# 11_MCU.net
KiCad netlist of a schematic drawn in Altium Designer
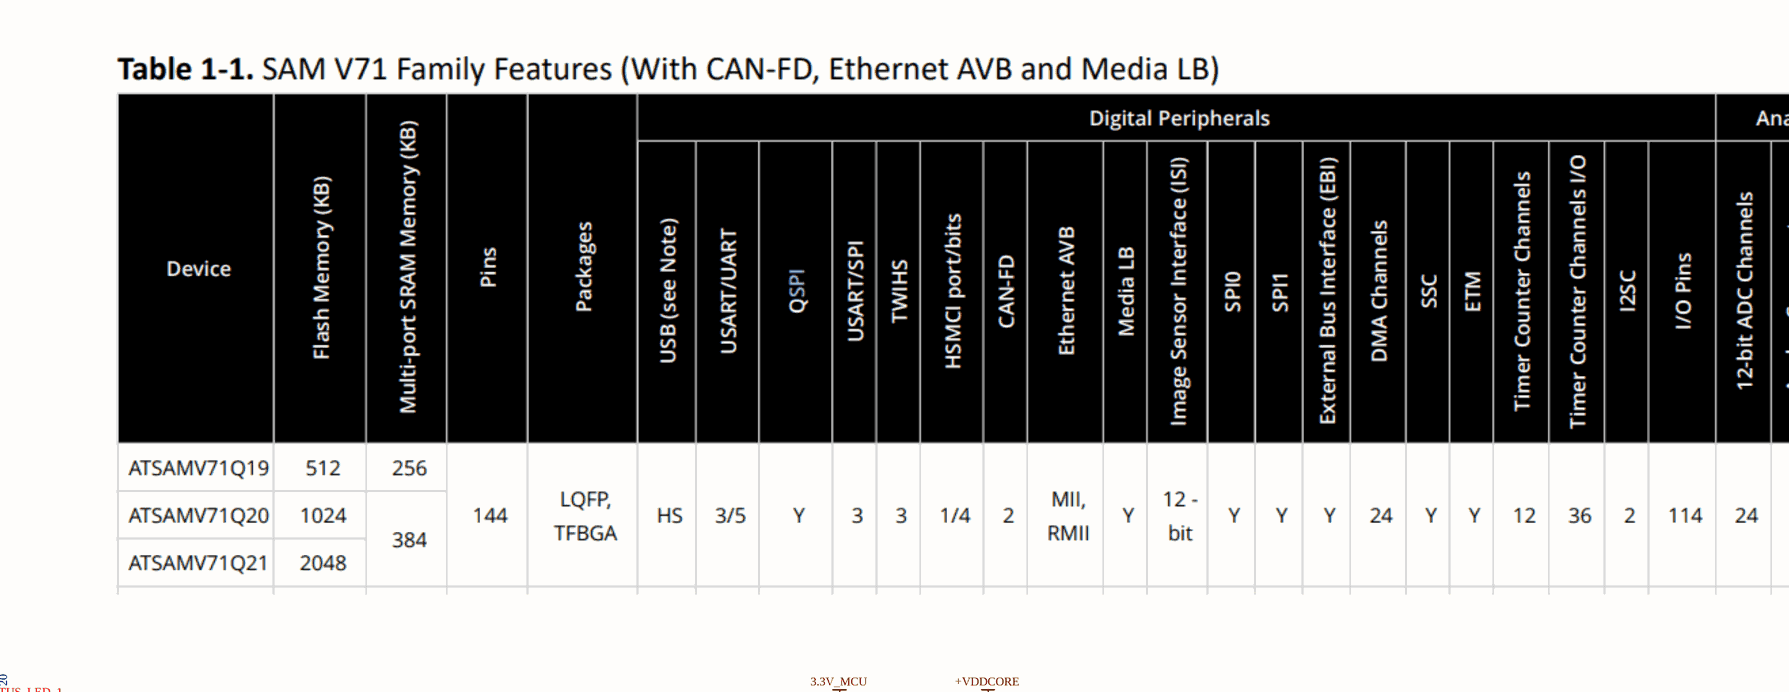
[diagram p0: 11_MCU.SchDoc, top left]
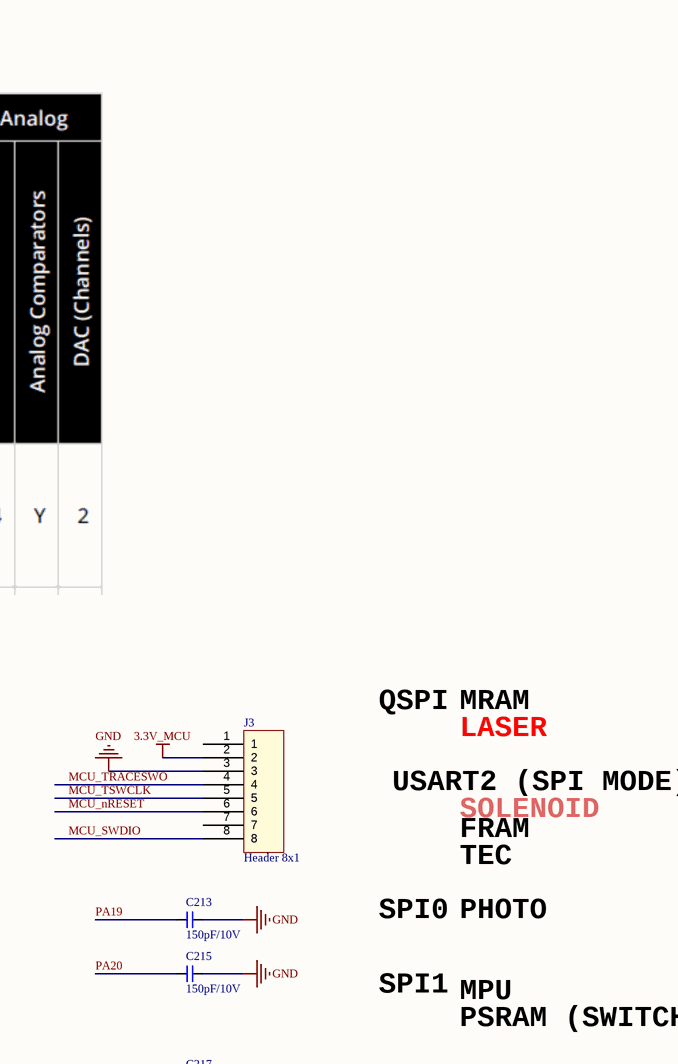
[diagram p1: 11_MCU.SchDoc, top right]
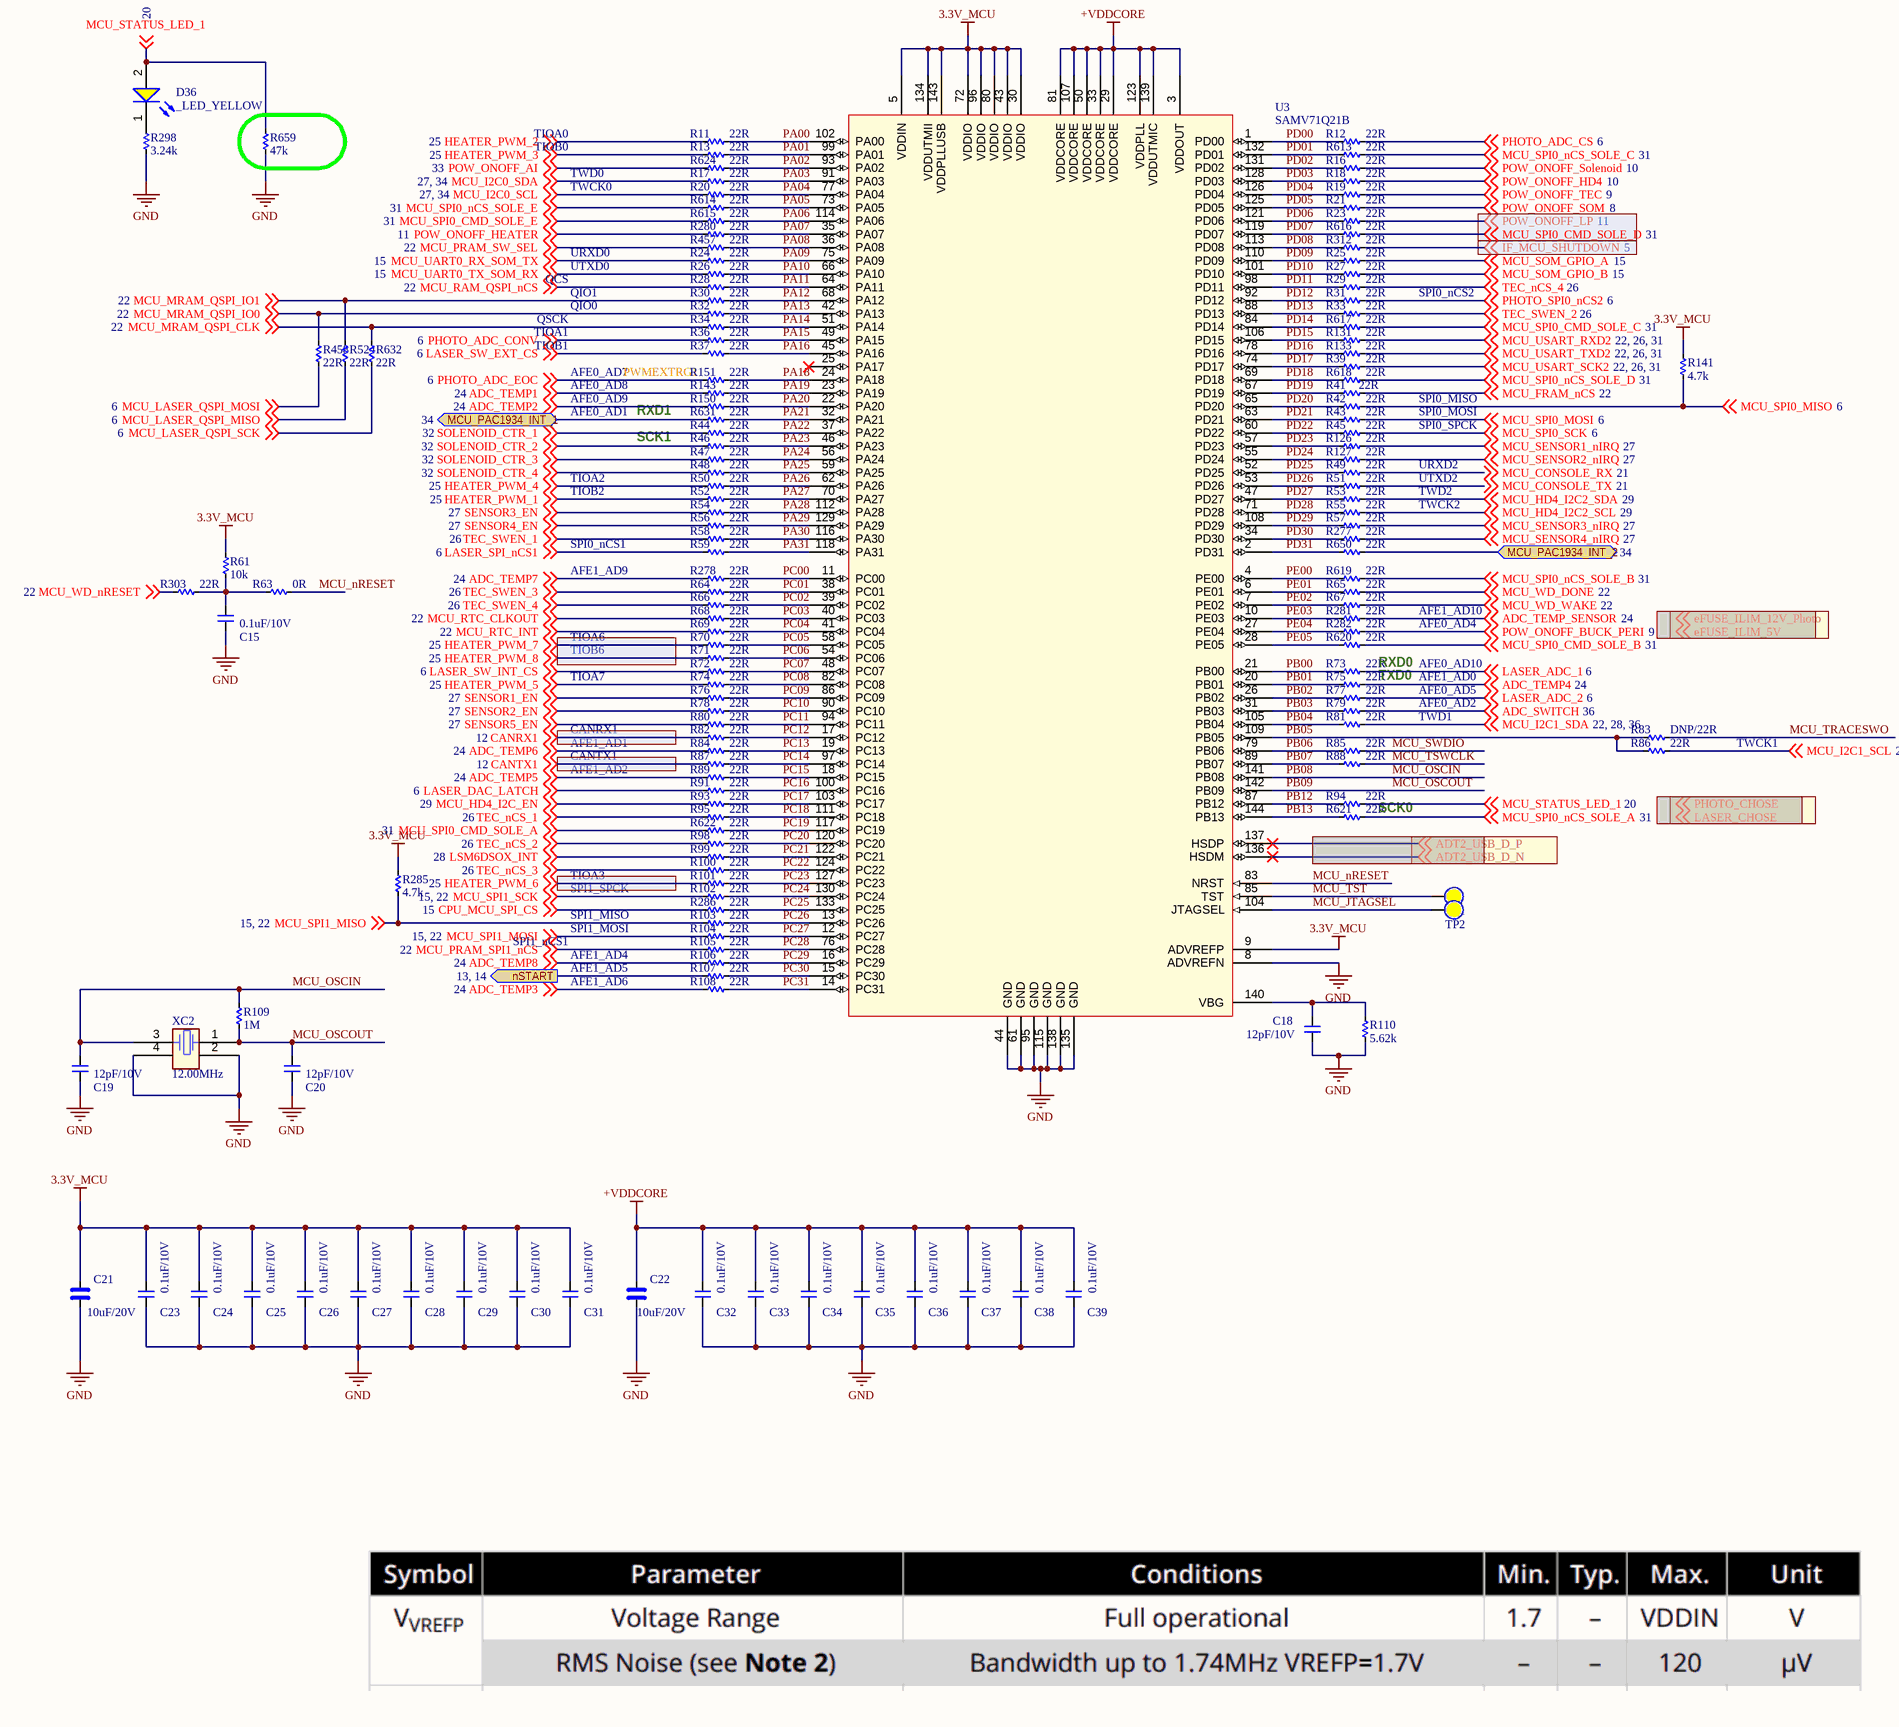
[diagram p2: 11_MCU.SchDoc, bottom left]
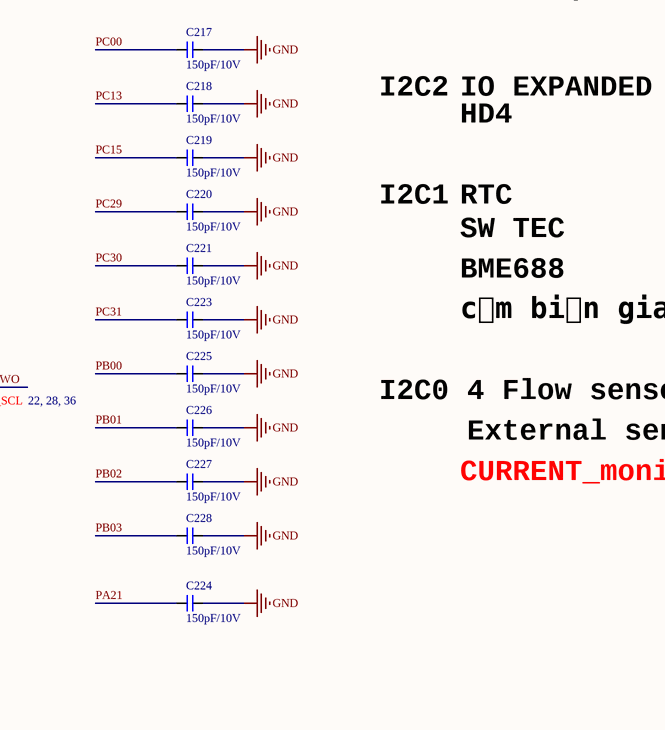
[diagram p3: 11_MCU.SchDoc, bottom right]

(export (version "E")
  (design (tool "Eeschema 10.0.6"))
  (components
    (comp (ref "C15")
      (value "0.1uF/10V")
      (footprint "CAP_C_1005X60")
      (description "CAP")
      (libsource (lib "LABLIB") (part "_CAP_C_2"))
    )
    (comp (ref "C18")
      (value "12pF/10V")
      (footprint "CAP_C_1005X60")
      (description "CAP")
      (libsource (lib "LABLIB") (part "_CAP_C_2"))
    )
    (comp (ref "C19")
      (value "12pF/10V")
      (footprint "CAP_C_1005X60")
      (description "CAP")
      (libsource (lib "LABLIB") (part "_CAP_C_2"))
    )
    (comp (ref "C20")
      (value "12pF/10V")
      (footprint "CAP_C_1005X60")
      (description "CAP")
      (libsource (lib "LABLIB") (part "_CAP_C_2"))
    )
    (comp (ref "C21")
      (value "10uF/20V")
      (footprint "CAP_C_2012X110")
      (description "CAP High Value")
      (libsource (lib "LABLIB") (part "_CAP_C_High_2"))
    )
    (comp (ref "C22")
      (value "10uF/20V")
      (footprint "CAP_C_2012X110")
      (description "CAP High Value")
      (libsource (lib "LABLIB") (part "_CAP_C_High_2"))
    )
    (comp (ref "C23")
      (value "0.1uF/10V")
      (footprint "CAP_C_1005X60")
      (description "CAP")
      (libsource (lib "LABLIB") (part "_CAP_C_2"))
    )
    (comp (ref "C24")
      (value "0.1uF/10V")
      (footprint "CAP_C_1005X60")
      (description "CAP")
      (libsource (lib "LABLIB") (part "_CAP_C_2"))
    )
    (comp (ref "C25")
      (value "0.1uF/10V")
      (footprint "CAP_C_1005X60")
      (description "CAP")
      (libsource (lib "LABLIB") (part "_CAP_C_2"))
    )
    (comp (ref "C26")
      (value "0.1uF/10V")
      (footprint "CAP_C_1005X60")
      (description "CAP")
      (libsource (lib "LABLIB") (part "_CAP_C_2"))
    )
    (comp (ref "C27")
      (value "0.1uF/10V")
      (footprint "CAP_C_1005X60")
      (description "CAP")
      (libsource (lib "LABLIB") (part "_CAP_C_2"))
    )
    (comp (ref "C28")
      (value "0.1uF/10V")
      (footprint "CAP_C_1005X60")
      (description "CAP")
      (libsource (lib "LABLIB") (part "_CAP_C_2"))
    )
    (comp (ref "C29")
      (value "0.1uF/10V")
      (footprint "CAP_C_1005X60")
      (description "CAP")
      (libsource (lib "LABLIB") (part "_CAP_C_2"))
    )
    (comp (ref "C30")
      (value "0.1uF/10V")
      (footprint "CAP_C_1005X60")
      (description "CAP")
      (libsource (lib "LABLIB") (part "_CAP_C_2"))
    )
    (comp (ref "C31")
      (value "0.1uF/10V")
      (footprint "CAP_C_1005X60")
      (description "CAP")
      (libsource (lib "LABLIB") (part "_CAP_C_2"))
    )
    (comp (ref "C32")
      (value "0.1uF/10V")
      (footprint "CAP_C_1005X60")
      (description "CAP")
      (libsource (lib "LABLIB") (part "_CAP_C_2"))
    )
    (comp (ref "C33")
      (value "0.1uF/10V")
      (footprint "CAP_C_1005X60")
      (description "CAP")
      (libsource (lib "LABLIB") (part "_CAP_C_2"))
    )
    (comp (ref "C34")
      (value "0.1uF/10V")
      (footprint "CAP_C_1005X60")
      (description "CAP")
      (libsource (lib "LABLIB") (part "_CAP_C_2"))
    )
    (comp (ref "C35")
      (value "0.1uF/10V")
      (footprint "CAP_C_1005X60")
      (description "CAP")
      (libsource (lib "LABLIB") (part "_CAP_C_2"))
    )
    (comp (ref "C36")
      (value "0.1uF/10V")
      (footprint "CAP_C_1005X60")
      (description "CAP")
      (libsource (lib "LABLIB") (part "_CAP_C_2"))
    )
    (comp (ref "C37")
      (value "0.1uF/10V")
      (footprint "CAP_C_1005X60")
      (description "CAP")
      (libsource (lib "LABLIB") (part "_CAP_C_2"))
    )
    (comp (ref "C38")
      (value "0.1uF/10V")
      (footprint "CAP_C_1005X60")
      (description "CAP")
      (libsource (lib "LABLIB") (part "_CAP_C_2"))
    )
    (comp (ref "C39")
      (value "0.1uF/10V")
      (footprint "CAP_C_1005X60")
      (description "CAP")
      (libsource (lib "LABLIB") (part "_CAP_C_2"))
    )
    (comp (ref "C213")
      (value "150pF/10V")
      (footprint "CAP_C_1005X60")
      (description "CAP")
      (libsource (lib "LABLIB") (part "_CAP_C_2"))
    )
    (comp (ref "C215")
      (value "150pF/10V")
      (footprint "CAP_C_1005X60")
      (description "CAP")
      (libsource (lib "LABLIB") (part "_CAP_C_2"))
    )
    (comp (ref "C217")
      (value "150pF/10V")
      (footprint "CAP_C_1005X60")
      (description "CAP")
      (libsource (lib "LABLIB") (part "_CAP_C_2"))
    )
    (comp (ref "C218")
      (value "150pF/10V")
      (footprint "CAP_C_1005X60")
      (description "CAP")
      (libsource (lib "LABLIB") (part "_CAP_C_2"))
    )
    (comp (ref "C219")
      (value "150pF/10V")
      (footprint "CAP_C_1005X60")
      (description "CAP")
      (libsource (lib "LABLIB") (part "_CAP_C_2"))
    )
    (comp (ref "C220")
      (value "150pF/10V")
      (footprint "CAP_C_1005X60")
      (description "CAP")
      (libsource (lib "LABLIB") (part "_CAP_C_2"))
    )
    (comp (ref "C221")
      (value "150pF/10V")
      (footprint "CAP_C_1005X60")
      (description "CAP")
      (libsource (lib "LABLIB") (part "_CAP_C_2"))
    )
    (comp (ref "C223")
      (value "150pF/10V")
      (footprint "CAP_C_1005X60")
      (description "CAP")
      (libsource (lib "LABLIB") (part "_CAP_C_2"))
    )
    (comp (ref "C224")
      (value "150pF/10V")
      (footprint "CAP_C_1005X60")
      (description "CAP")
      (libsource (lib "LABLIB") (part "_CAP_C_2"))
    )
    (comp (ref "C225")
      (value "150pF/10V")
      (footprint "CAP_C_1005X60")
      (description "CAP")
      (libsource (lib "LABLIB") (part "_CAP_C_2"))
    )
    (comp (ref "C226")
      (value "150pF/10V")
      (footprint "CAP_C_1005X60")
      (description "CAP")
      (libsource (lib "LABLIB") (part "_CAP_C_2"))
    )
    (comp (ref "C227")
      (value "150pF/10V")
      (footprint "CAP_C_1005X60")
      (description "CAP")
      (libsource (lib "LABLIB") (part "_CAP_C_2"))
    )
    (comp (ref "C228")
      (value "150pF/10V")
      (footprint "CAP_C_1005X60")
      (description "CAP")
      (libsource (lib "LABLIB") (part "_CAP_C_2"))
    )
    (comp (ref "D36")
      (value "_LED_YELLOW")
      (footprint "LED_0603")
      (libsource (lib "LABLIB") (part "_LED_YELLOW"))
    )
    (comp (ref "J3")
      (value "Header 8x1")
      (footprint "Header_254P_8x1")
      (libsource (lib "LABLIB") (part "Header 8x1"))
    )
    (comp (ref "R11")
      (value "22R")
      (footprint "RES_C_1005X40")
      (description "RES")
      (libsource (lib "LABLIB") (part "_RES_B_2"))
    )
    (comp (ref "R12")
      (value "22R")
      (footprint "RES_C_1005X40")
      (description "RES")
      (libsource (lib "LABLIB") (part "_RES_B_2"))
    )
    (comp (ref "R13")
      (value "22R")
      (footprint "RES_C_1005X40")
      (description "RES")
      (libsource (lib "LABLIB") (part "_RES_B_2"))
    )
    (comp (ref "R16")
      (value "22R")
      (footprint "RES_C_1005X40")
      (description "RES")
      (libsource (lib "LABLIB") (part "_RES_B_2"))
    )
    (comp (ref "R17")
      (value "22R")
      (footprint "RES_C_1005X40")
      (description "RES")
      (libsource (lib "LABLIB") (part "_RES_B_2"))
    )
    (comp (ref "R18")
      (value "22R")
      (footprint "RES_C_1005X40")
      (description "RES")
      (libsource (lib "LABLIB") (part "_RES_B_2"))
    )
    (comp (ref "R19")
      (value "22R")
      (footprint "RES_C_1005X40")
      (description "RES")
      (libsource (lib "LABLIB") (part "_RES_B_2"))
    )
    (comp (ref "R20")
      (value "22R")
      (footprint "RES_C_1005X40")
      (description "RES")
      (libsource (lib "LABLIB") (part "_RES_B_2"))
    )
    (comp (ref "R21")
      (value "22R")
      (footprint "RES_C_1005X40")
      (description "RES")
      (libsource (lib "LABLIB") (part "_RES_B_2"))
    )
    (comp (ref "R23")
      (value "22R")
      (footprint "RES_C_1005X40")
      (description "RES")
      (libsource (lib "LABLIB") (part "_RES_B_2"))
    )
    (comp (ref "R24")
      (value "22R")
      (footprint "RES_C_1005X40")
      (description "RES")
      (libsource (lib "LABLIB") (part "_RES_B_2"))
    )
    (comp (ref "R25")
      (value "22R")
      (footprint "RES_C_1005X40")
      (description "RES")
      (libsource (lib "LABLIB") (part "_RES_B_2"))
    )
    (comp (ref "R26")
      (value "22R")
      (footprint "RES_C_1005X40")
      (description "RES")
      (libsource (lib "LABLIB") (part "_RES_B_2"))
    )
    (comp (ref "R27")
      (value "22R")
      (footprint "RES_C_1005X40")
      (description "RES")
      (libsource (lib "LABLIB") (part "_RES_B_2"))
    )
    (comp (ref "R28")
      (value "22R")
      (footprint "RES_C_1005X40")
      (description "RES")
      (libsource (lib "LABLIB") (part "_RES_B_2"))
    )
    (comp (ref "R29")
      (value "22R")
      (footprint "RES_C_1005X40")
      (description "RES")
      (libsource (lib "LABLIB") (part "_RES_B_2"))
    )
    (comp (ref "R30")
      (value "22R")
      (footprint "RES_C_1005X40")
      (description "RES")
      (libsource (lib "LABLIB") (part "_RES_B_2"))
    )
    (comp (ref "R31")
      (value "22R")
      (footprint "RES_C_1005X40")
      (description "RES")
      (libsource (lib "LABLIB") (part "_RES_B_2"))
    )
    (comp (ref "R32")
      (value "22R")
      (footprint "RES_C_1005X40")
      (description "RES")
      (libsource (lib "LABLIB") (part "_RES_B_2"))
    )
    (comp (ref "R33")
      (value "22R")
      (footprint "RES_C_1005X40")
      (description "RES")
      (libsource (lib "LABLIB") (part "_RES_B_2"))
    )
    (comp (ref "R34")
      (value "22R")
      (footprint "RES_C_1005X40")
      (description "RES")
      (libsource (lib "LABLIB") (part "_RES_B_2"))
    )
    (comp (ref "R36")
      (value "22R")
      (footprint "RES_C_1005X40")
      (description "RES")
      (libsource (lib "LABLIB") (part "_RES_B_2"))
    )
    (comp (ref "R37")
      (value "22R")
      (footprint "RES_C_1005X40")
      (description "RES")
      (libsource (lib "LABLIB") (part "_RES_B_2"))
    )
    (comp (ref "R39")
      (value "22R")
      (footprint "RES_C_1005X40")
      (description "RES")
      (libsource (lib "LABLIB") (part "_RES_B_2"))
    )
    (comp (ref "R41")
      (value "22R")
      (footprint "RES_C_1005X40")
      (description "RES")
      (libsource (lib "LABLIB") (part "_RES_B_2"))
    )
    (comp (ref "R42")
      (value "22R")
      (footprint "RES_C_1005X40")
      (description "RES")
      (libsource (lib "LABLIB") (part "_RES_B_2"))
    )
    (comp (ref "R43")
      (value "22R")
      (footprint "RES_C_1005X40")
      (description "RES")
      (libsource (lib "LABLIB") (part "_RES_B_2"))
    )
    (comp (ref "R44")
      (value "22R")
      (footprint "RES_C_1005X40")
      (description "RES")
      (libsource (lib "LABLIB") (part "_RES_B_2"))
    )
    (comp (ref "R45")
      (value "22R")
      (footprint "RES_C_1005X40")
      (description "RES")
      (libsource (lib "LABLIB") (part "_RES_B_2"))
    )
    (comp (ref "R46")
      (value "22R")
      (footprint "RES_C_1005X40")
      (description "RES")
      (libsource (lib "LABLIB") (part "_RES_B_2"))
    )
    (comp (ref "R47")
      (value "22R")
      (footprint "RES_C_1005X40")
      (description "RES")
      (libsource (lib "LABLIB") (part "_RES_B_2"))
    )
    (comp (ref "R48")
      (value "22R")
      (footprint "RES_C_1005X40")
      (description "RES")
      (libsource (lib "LABLIB") (part "_RES_B_2"))
    )
    (comp (ref "R49")
      (value "22R")
      (footprint "RES_C_1005X40")
      (description "RES")
      (libsource (lib "LABLIB") (part "_RES_B_2"))
    )
    (comp (ref "R50")
      (value "22R")
      (footprint "RES_C_1005X40")
      (description "RES")
      (libsource (lib "LABLIB") (part "_RES_B_2"))
    )
    (comp (ref "R51")
      (value "22R")
      (footprint "RES_C_1005X40")
      (description "RES")
      (libsource (lib "LABLIB") (part "_RES_B_2"))
    )
    (comp (ref "R52")
      (value "22R")
      (footprint "RES_C_1005X40")
      (description "RES")
      (libsource (lib "LABLIB") (part "_RES_B_2"))
    )
    (comp (ref "R53")
      (value "22R")
      (footprint "RES_C_1005X40")
      (description "RES")
      (libsource (lib "LABLIB") (part "_RES_B_2"))
    )
    (comp (ref "R54")
      (value "22R")
      (footprint "RES_C_1005X40")
      (description "RES")
      (libsource (lib "LABLIB") (part "_RES_B_2"))
    )
    (comp (ref "R55")
      (value "22R")
      (footprint "RES_C_1005X40")
      (description "RES")
      (libsource (lib "LABLIB") (part "_RES_B_2"))
    )
    (comp (ref "R56")
      (value "22R")
      (footprint "RES_C_1005X40")
      (description "RES")
      (libsource (lib "LABLIB") (part "_RES_B_2"))
    )
    (comp (ref "R57")
      (value "22R")
      (footprint "RES_C_1005X40")
      (description "RES")
      (libsource (lib "LABLIB") (part "_RES_B_2"))
    )
    (comp (ref "R58")
      (value "22R")
      (footprint "RES_C_1005X40")
      (description "RES")
      (libsource (lib "LABLIB") (part "_RES_B_2"))
    )
    (comp (ref "R59")
      (value "22R")
      (footprint "RES_C_1005X40")
      (description "RES")
      (libsource (lib "LABLIB") (part "_RES_B_2"))
    )
    (comp (ref "R61")
      (value "10k")
      (footprint "RES_C_1005X40")
      (description "RES")
      (libsource (lib "LABLIB") (part "_RES_B_2"))
    )
    (comp (ref "R63")
      (value "0R")
      (footprint "RES_C_1005X40")
      (description "RES")
      (libsource (lib "LABLIB") (part "_RES_B_2"))
    )
    (comp (ref "R64")
      (value "22R")
      (footprint "RES_C_1005X40")
      (description "RES")
      (libsource (lib "LABLIB") (part "_RES_B_2"))
    )
    (comp (ref "R65")
      (value "22R")
      (footprint "RES_C_1005X40")
      (description "RES")
      (libsource (lib "LABLIB") (part "_RES_B_2"))
    )
    (comp (ref "R66")
      (value "22R")
      (footprint "RES_C_1005X40")
      (description "RES")
      (libsource (lib "LABLIB") (part "_RES_B_2"))
    )
    (comp (ref "R67")
      (value "22R")
      (footprint "RES_C_1005X40")
      (description "RES")
      (libsource (lib "LABLIB") (part "_RES_B_2"))
    )
    (comp (ref "R68")
      (value "22R")
      (footprint "RES_C_1005X40")
      (description "RES")
      (libsource (lib "LABLIB") (part "_RES_B_2"))
    )
    (comp (ref "R69")
      (value "22R")
      (footprint "RES_C_1005X40")
      (description "RES")
      (libsource (lib "LABLIB") (part "_RES_B_2"))
    )
    (comp (ref "R70")
      (value "22R")
      (footprint "RES_C_1005X40")
      (description "RES")
      (libsource (lib "LABLIB") (part "_RES_B_2"))
    )
    (comp (ref "R71")
      (value "22R")
      (footprint "RES_C_1005X40")
      (description "RES")
      (libsource (lib "LABLIB") (part "_RES_B_2"))
    )
    (comp (ref "R72")
      (value "22R")
      (footprint "RES_C_1005X40")
      (description "RES")
      (libsource (lib "LABLIB") (part "_RES_B_2"))
    )
    (comp (ref "R73")
      (value "22R")
      (footprint "RES_C_1005X40")
      (description "RES")
      (libsource (lib "LABLIB") (part "_RES_B_2"))
    )
    (comp (ref "R74")
      (value "22R")
      (footprint "RES_C_1005X40")
      (description "RES")
      (libsource (lib "LABLIB") (part "_RES_B_2"))
    )
    (comp (ref "R75")
      (value "22R")
      (footprint "RES_C_1005X40")
      (description "RES")
      (libsource (lib "LABLIB") (part "_RES_B_2"))
    )
    (comp (ref "R76")
      (value "22R")
      (footprint "RES_C_1005X40")
      (description "RES")
      (libsource (lib "LABLIB") (part "_RES_B_2"))
    )
    (comp (ref "R77")
      (value "22R")
      (footprint "RES_C_1005X40")
      (description "RES")
      (libsource (lib "LABLIB") (part "_RES_B_2"))
    )
    (comp (ref "R78")
      (value "22R")
      (footprint "RES_C_1005X40")
      (description "RES")
      (libsource (lib "LABLIB") (part "_RES_B_2"))
    )
    (comp (ref "R79")
      (value "22R")
      (footprint "RES_C_1005X40")
      (description "RES")
      (libsource (lib "LABLIB") (part "_RES_B_2"))
    )
    (comp (ref "R80")
      (value "22R")
      (footprint "RES_C_1005X40")
      (description "RES")
      (libsource (lib "LABLIB") (part "_RES_B_2"))
    )
    (comp (ref "R81")
      (value "22R")
      (footprint "RES_C_1005X40")
      (description "RES")
      (libsource (lib "LABLIB") (part "_RES_B_2"))
    )
    (comp (ref "R82")
      (value "22R")
      (footprint "RES_C_1005X40")
      (description "RES")
      (libsource (lib "LABLIB") (part "_RES_B_2"))
    )
    (comp (ref "R83")
      (value "DNP/22R")
      (footprint "RES_C_1005X40")
      (description "RES")
      (libsource (lib "LABLIB") (part "_RES_B_2"))
    )
    (comp (ref "R84")
      (value "22R")
      (footprint "RES_C_1005X40")
      (description "RES")
      (libsource (lib "LABLIB") (part "_RES_B_2"))
    )
    (comp (ref "R85")
      (value "22R")
      (footprint "RES_C_1005X40")
      (description "RES")
      (libsource (lib "LABLIB") (part "_RES_B_2"))
    )
    (comp (ref "R86")
      (value "22R")
      (footprint "RES_C_1005X40")
      (description "RES")
      (libsource (lib "LABLIB") (part "_RES_B_2"))
    )
    (comp (ref "R87")
      (value "22R")
      (footprint "RES_C_1005X40")
      (description "RES")
      (libsource (lib "LABLIB") (part "_RES_B_2"))
    )
    (comp (ref "R88")
      (value "22R")
      (footprint "RES_C_1005X40")
      (description "RES")
      (libsource (lib "LABLIB") (part "_RES_B_2"))
    )
    (comp (ref "R89")
      (value "22R")
      (footprint "RES_C_1005X40")
      (description "RES")
      (libsource (lib "LABLIB") (part "_RES_B_2"))
    )
    (comp (ref "R91")
      (value "22R")
      (footprint "RES_C_1005X40")
      (description "RES")
      (libsource (lib "LABLIB") (part "_RES_B_2"))
    )
    (comp (ref "R93")
      (value "22R")
      (footprint "RES_C_1005X40")
      (description "RES")
      (libsource (lib "LABLIB") (part "_RES_B_2"))
    )
    (comp (ref "R94")
      (value "22R")
      (footprint "RES_C_1005X40")
      (description "RES")
      (libsource (lib "LABLIB") (part "_RES_B_2"))
    )
    (comp (ref "R95")
      (value "22R")
      (footprint "RES_C_1005X40")
      (description "RES")
      (libsource (lib "LABLIB") (part "_RES_B_2"))
    )
    (comp (ref "R98")
      (value "22R")
      (footprint "RES_C_1005X40")
      (description "RES")
      (libsource (lib "LABLIB") (part "_RES_B_2"))
    )
    (comp (ref "R99")
      (value "22R")
      (footprint "RES_C_1005X40")
      (description "RES")
      (libsource (lib "LABLIB") (part "_RES_B_2"))
    )
    (comp (ref "R100")
      (value "22R")
      (footprint "RES_C_1005X40")
      (description "RES")
      (libsource (lib "LABLIB") (part "_RES_B_2"))
    )
    (comp (ref "R101")
      (value "22R")
      (footprint "RES_C_1005X40")
      (description "RES")
      (libsource (lib "LABLIB") (part "_RES_B_2"))
    )
    (comp (ref "R102")
      (value "22R")
      (footprint "RES_C_1005X40")
      (description "RES")
      (libsource (lib "LABLIB") (part "_RES_B_2"))
    )
    (comp (ref "R103")
      (value "22R")
      (footprint "RES_C_1005X40")
      (description "RES")
      (libsource (lib "LABLIB") (part "_RES_B_2"))
    )
    (comp (ref "R104")
      (value "22R")
      (footprint "RES_C_1005X40")
      (description "RES")
      (libsource (lib "LABLIB") (part "_RES_B_2"))
    )
    (comp (ref "R105")
      (value "22R")
      (footprint "RES_C_1005X40")
      (description "RES")
      (libsource (lib "LABLIB") (part "_RES_B_2"))
    )
    (comp (ref "R106")
      (value "22R")
      (footprint "RES_C_1005X40")
      (description "RES")
      (libsource (lib "LABLIB") (part "_RES_B_2"))
    )
    (comp (ref "R107")
      (value "22R")
      (footprint "RES_C_1005X40")
      (description "RES")
      (libsource (lib "LABLIB") (part "_RES_B_2"))
    )
    (comp (ref "R108")
      (value "22R")
      (footprint "RES_C_1005X40")
      (description "RES")
      (libsource (lib "LABLIB") (part "_RES_B_2"))
    )
    (comp (ref "R109")
      (value "1M")
      (footprint "RES_C_1005X40")
      (description "RES")
      (libsource (lib "LABLIB") (part "_RES_B_2"))
    )
    (comp (ref "R110")
      (value "5.62k")
      (footprint "RES_C_1005X40")
      (description "RES")
      (libsource (lib "LABLIB") (part "_RES_B_2"))
    )
    (comp (ref "R126")
      (value "22R")
      (footprint "RES_C_1005X40")
      (description "RES")
      (libsource (lib "LABLIB") (part "_RES_B_2"))
    )
    (comp (ref "R127")
      (value "22R")
      (footprint "RES_C_1005X40")
      (description "RES")
      (libsource (lib "LABLIB") (part "_RES_B_2"))
    )
    (comp (ref "R131")
      (value "22R")
      (footprint "RES_C_1005X40")
      (description "RES")
      (libsource (lib "LABLIB") (part "_RES_B_2"))
    )
    (comp (ref "R133")
      (value "22R")
      (footprint "RES_C_1005X40")
      (description "RES")
      (libsource (lib "LABLIB") (part "_RES_B_2"))
    )
    (comp (ref "R141")
      (value "4.7k")
      (footprint "RES_C_1005X40")
      (description "RES")
      (libsource (lib "LABLIB") (part "_RES_B_2"))
    )
    (comp (ref "R143")
      (value "22R")
      (footprint "RES_C_1005X40")
      (description "RES")
      (libsource (lib "LABLIB") (part "_RES_B_2"))
    )
    (comp (ref "R150")
      (value "22R")
      (footprint "RES_C_1005X40")
      (description "RES")
      (libsource (lib "LABLIB") (part "_RES_B_2"))
    )
    (comp (ref "R151")
      (value "22R")
      (footprint "RES_C_1005X40")
      (description "RES")
      (libsource (lib "LABLIB") (part "_RES_B_2"))
    )
    (comp (ref "R277")
      (value "22R")
      (footprint "RES_C_1005X40")
      (description "RES")
      (libsource (lib "LABLIB") (part "_RES_B_2"))
    )
    (comp (ref "R278")
      (value "22R")
      (footprint "RES_C_1005X40")
      (description "RES")
      (libsource (lib "LABLIB") (part "_RES_B_2"))
    )
    (comp (ref "R280")
      (value "22R")
      (footprint "RES_C_1005X40")
      (description "RES")
      (libsource (lib "LABLIB") (part "_RES_B_2"))
    )
    (comp (ref "R281")
      (value "22R")
      (footprint "RES_C_1005X40")
      (description "RES")
      (libsource (lib "LABLIB") (part "_RES_B_2"))
    )
    (comp (ref "R282")
      (value "22R")
      (footprint "RES_C_1005X40")
      (description "RES")
      (libsource (lib "LABLIB") (part "_RES_B_2"))
    )
    (comp (ref "R285")
      (value "4.7k")
      (footprint "RES_C_1005X40")
      (description "RES")
      (libsource (lib "LABLIB") (part "_RES_B_2"))
    )
    (comp (ref "R286")
      (value "22R")
      (footprint "RES_C_1005X40")
      (description "RES")
      (libsource (lib "LABLIB") (part "_RES_B_2"))
    )
    (comp (ref "R298")
      (value "3.24k")
      (footprint "RES_C_1005X40")
      (description "RES")
      (libsource (lib "LABLIB") (part "_RES_B_2"))
    )
    (comp (ref "R303")
      (value "22R")
      (footprint "RES_C_1005X40")
      (description "RES")
      (libsource (lib "LABLIB") (part "_RES_B_2"))
    )
    (comp (ref "R312")
      (value "22R")
      (footprint "RES_C_1005X40")
      (description "RES")
      (libsource (lib "LABLIB") (part "_RES_B_2"))
    )
    (comp (ref "R457")
      (value "22R")
      (footprint "RES_C_1005X40")
      (description "RES")
      (libsource (lib "LABLIB") (part "_RES_B_2"))
    )
    (comp (ref "R458")
      (value "22R")
      (footprint "RES_C_1005X40")
      (description "RES")
      (libsource (lib "LABLIB") (part "_RES_B_2"))
    )
    (comp (ref "R524")
      (value "22R")
      (footprint "RES_C_1005X40")
      (description "RES")
      (libsource (lib "LABLIB") (part "_RES_B_2"))
    )
    (comp (ref "R613")
      (value "22R")
      (footprint "RES_C_1005X40")
      (description "RES")
      (libsource (lib "LABLIB") (part "_RES_B_2"))
    )
    (comp (ref "R614")
      (value "22R")
      (footprint "RES_C_1005X40")
      (description "RES")
      (libsource (lib "LABLIB") (part "_RES_B_2"))
    )
    (comp (ref "R615")
      (value "22R")
      (footprint "RES_C_1005X40")
      (description "RES")
      (libsource (lib "LABLIB") (part "_RES_B_2"))
    )
    (comp (ref "R616")
      (value "22R")
      (footprint "RES_C_1005X40")
      (description "RES")
      (libsource (lib "LABLIB") (part "_RES_B_2"))
    )
    (comp (ref "R617")
      (value "22R")
      (footprint "RES_C_1005X40")
      (description "RES")
      (libsource (lib "LABLIB") (part "_RES_B_2"))
    )
    (comp (ref "R618")
      (value "22R")
      (footprint "RES_C_1005X40")
      (description "RES")
      (libsource (lib "LABLIB") (part "_RES_B_2"))
    )
    (comp (ref "R619")
      (value "22R")
      (footprint "RES_C_1005X40")
      (description "RES")
      (libsource (lib "LABLIB") (part "_RES_B_2"))
    )
    (comp (ref "R620")
      (value "22R")
      (footprint "RES_C_1005X40")
      (description "RES")
      (libsource (lib "LABLIB") (part "_RES_B_2"))
    )
    (comp (ref "R621")
      (value "22R")
      (footprint "RES_C_1005X40")
      (description "RES")
      (libsource (lib "LABLIB") (part "_RES_B_2"))
    )
    (comp (ref "R622")
      (value "22R")
      (footprint "RES_C_1005X40")
      (description "RES")
      (libsource (lib "LABLIB") (part "_RES_B_2"))
    )
    (comp (ref "R624")
      (value "22R")
      (footprint "RES_C_1005X40")
      (description "RES")
      (libsource (lib "LABLIB") (part "_RES_B_2"))
    )
    (comp (ref "R631")
      (value "22R")
      (footprint "RES_C_1005X40")
      (description "RES")
      (libsource (lib "LABLIB") (part "_RES_B_2"))
    )
    (comp (ref "R632")
      (value "22R")
      (footprint "RES_C_1005X40")
      (description "RES")
      (libsource (lib "LABLIB") (part "_RES_B_2"))
    )
    (comp (ref "R650")
      (value "22R")
      (footprint "RES_C_1005X40")
      (description "RES")
      (libsource (lib "LABLIB") (part "_RES_B_2"))
    )
    (comp (ref "R659")
      (value "47k")
      (footprint "RES_C_1608X60")
      (description "RES")
      (libsource (lib "LABLIB") (part "_RES_B_2"))
    )
    (comp (ref "TP1")
      (value "~")
      (footprint "Testpoint_80")
      (description "Test Point")
      (libsource (lib "LABLIB") (part "Test Point"))
    )
    (comp (ref "TP2")
      (value "~")
      (footprint "Testpoint_80")
      (description "Test Point")
      (libsource (lib "LABLIB") (part "Test Point"))
    )
    (comp (ref "U3")
      (value "SAMV71Q21B")
      (footprint "AP6-00118")
      (description "SAM 32-bit ARM Cortex-M* RISC MCU, SAMV71B Series, QFP144")
      (fields (field (name "MANUFACTURER") "MICROCHIP") (field (name "MPN") "ATSAMV71Q21B-AAB"))
      (libsource (lib "AltiumDbLib") (part "SAMV7_LQFP144"))
    )
    (comp (ref "XC2")
      (value "12.00MHz")
      (footprint "AP7-00039")
      (description "Fox FQ5032B 12.0MHz SMD crystal 738B-12")
      (fields (field (name "TOLERANCE") "Â±30ppm") (field (name "MANUFACTURER") "Fox  Electronics"))
      (libsource (lib "AltiumDbLib") (part "CRYSTAL1324"))
    )
  )
  (nets
    (net (code "1") (name "+VDDCORE") (class "Default")
      (node (ref "C22") (pin "1") (pinfunction "1_1") (pintype "passive"))
      (node (ref "C32") (pin "2") (pinfunction "2_2") (pintype "passive"))
      (node (ref "C33") (pin "2") (pinfunction "2_2") (pintype "passive"))
      (node (ref "C34") (pin "2") (pinfunction "2_2") (pintype "passive"))
      (node (ref "C35") (pin "2") (pinfunction "2_2") (pintype "passive"))
      (node (ref "C36") (pin "2") (pinfunction "2_2") (pintype "passive"))
      (node (ref "C37") (pin "2") (pinfunction "2_2") (pintype "passive"))
      (node (ref "C38") (pin "2") (pinfunction "2_2") (pintype "passive"))
      (node (ref "C39") (pin "2") (pinfunction "2_2") (pintype "passive"))
      (node (ref "U3") (pin "107") (pinfunction "VDDCORE_107") (pintype "power_in"))
      (node (ref "U3") (pin "123") (pinfunction "VDDPLL_123") (pintype "power_in"))
      (node (ref "U3") (pin "139") (pinfunction "VDDUTMIC_139") (pintype "power_in"))
      (node (ref "U3") (pin "29") (pinfunction "VDDCORE_29") (pintype "power_in"))
      (node (ref "U3") (pin "3") (pinfunction "VDDOUT_3") (pintype "power_in"))
      (node (ref "U3") (pin "33") (pinfunction "VDDCORE_33") (pintype "power_in"))
      (node (ref "U3") (pin "50") (pinfunction "VDDCORE_50") (pintype "power_in"))
      (node (ref "U3") (pin "81") (pinfunction "VDDCORE_81") (pintype "power_in"))
    )
    (net (code "2") (name "/MCU_JTAGSEL") (class "Default")
      (node (ref "TP2") (pin "1") (pinfunction "1_1") (pintype "passive"))
      (node (ref "U3") (pin "104") (pinfunction "JTAGSEL_104") (pintype "input"))
    )
    (net (code "3") (name "/MCU_OSCIN") (class "Default")
      (node (ref "C19") (pin "2") (pinfunction "2_2") (pintype "passive"))
      (node (ref "R109") (pin "2") (pinfunction "2_2") (pintype "passive"))
      (node (ref "U3") (pin "141") (pinfunction "PB08_141") (pintype "bidirectional"))
      (node (ref "XC2") (pin "3") (pinfunction "3_3") (pintype "passive"))
    )
    (net (code "4") (name "/MCU_OSCOUT") (class "Default")
      (node (ref "C20") (pin "2") (pinfunction "2_2") (pintype "passive"))
      (node (ref "R109") (pin "1") (pinfunction "1_1") (pintype "passive"))
      (node (ref "U3") (pin "142") (pinfunction "PB09_142") (pintype "bidirectional"))
      (node (ref "XC2") (pin "1") (pinfunction "1_1") (pintype "passive"))
    )
    (net (code "5") (name "/MCU_PAC1934_INT_1") (class "Default")
      (node (ref "R631") (pin "2") (pinfunction "2_2") (pintype "passive"))
    )
    (net (code "6") (name "/MCU_PAC1934_INT_2") (class "Default")
      (node (ref "R650") (pin "2") (pinfunction "2_2") (pintype "passive"))
    )
    (net (code "7") (name "/MCU_SWDIO") (class "Default")
      (node (ref "J3") (pin "8") (pinfunction "8_8") (pintype "passive"))
      (node (ref "R85") (pin "1") (pinfunction "1_1") (pintype "passive"))
    )
    (net (code "8") (name "/MCU_TRACESWO") (class "Default")
      (node (ref "J3") (pin "4") (pinfunction "4_4") (pintype "passive"))
      (node (ref "R83") (pin "1") (pinfunction "1_1") (pintype "passive"))
    )
    (net (code "9") (name "/MCU_TST") (class "Default")
      (node (ref "TP1") (pin "1") (pinfunction "1_1") (pintype "passive"))
      (node (ref "U3") (pin "85") (pinfunction "TST_85") (pintype "input"))
    )
    (net (code "10") (name "/MCU_TSWCLK") (class "Default")
      (node (ref "J3") (pin "5") (pinfunction "5_5") (pintype "passive"))
      (node (ref "R88") (pin "1") (pinfunction "1_1") (pintype "passive"))
    )
    (net (code "11") (name "/MCU_nRESET") (class "Default")
      (node (ref "J3") (pin "6") (pinfunction "6_6") (pintype "passive"))
      (node (ref "R63") (pin "1") (pinfunction "1_1") (pintype "passive"))
      (node (ref "U3") (pin "83") (pinfunction "NRST_83") (pintype "input"))
    )
    (net (code "12") (name "/PA00") (class "Default")
      (node (ref "R11") (pin "1") (pinfunction "1_1") (pintype "passive"))
      (node (ref "U3") (pin "102") (pinfunction "PA00_102") (pintype "bidirectional"))
    )
    (net (code "13") (name "/PA01") (class "Default")
      (node (ref "R13") (pin "1") (pinfunction "1_1") (pintype "passive"))
      (node (ref "U3") (pin "99") (pinfunction "PA01_99") (pintype "bidirectional"))
    )
    (net (code "14") (name "/PA02") (class "Default")
      (node (ref "R624") (pin "1") (pinfunction "1_1") (pintype "passive"))
      (node (ref "U3") (pin "93") (pinfunction "PA02_93") (pintype "bidirectional"))
    )
    (net (code "15") (name "/PA03") (class "Default")
      (node (ref "R17") (pin "1") (pinfunction "1_1") (pintype "passive"))
      (node (ref "U3") (pin "91") (pinfunction "PA03_91") (pintype "bidirectional"))
    )
    (net (code "16") (name "/PA04") (class "Default")
      (node (ref "R20") (pin "1") (pinfunction "1_1") (pintype "passive"))
      (node (ref "U3") (pin "77") (pinfunction "PA04_77") (pintype "bidirectional"))
    )
    (net (code "17") (name "/PA05") (class "Default")
      (node (ref "R614") (pin "1") (pinfunction "1_1") (pintype "passive"))
      (node (ref "U3") (pin "73") (pinfunction "PA05_73") (pintype "bidirectional"))
    )
    (net (code "18") (name "/PA06") (class "Default")
      (node (ref "R615") (pin "1") (pinfunction "1_1") (pintype "passive"))
      (node (ref "U3") (pin "114") (pinfunction "PA06_114") (pintype "bidirectional"))
    )
    (net (code "19") (name "/PA07") (class "Default")
      (node (ref "R280") (pin "1") (pinfunction "1_1") (pintype "passive"))
      (node (ref "U3") (pin "35") (pinfunction "PA07_35") (pintype "bidirectional"))
    )
    (net (code "20") (name "/PA08") (class "Default")
      (node (ref "R457") (pin "1") (pinfunction "1_1") (pintype "passive"))
      (node (ref "U3") (pin "36") (pinfunction "PA08_36") (pintype "bidirectional"))
    )
    (net (code "21") (name "/PA09") (class "Default")
      (node (ref "R24") (pin "1") (pinfunction "1_1") (pintype "passive"))
      (node (ref "U3") (pin "75") (pinfunction "PA09_75") (pintype "bidirectional"))
    )
    (net (code "22") (name "/PA10") (class "Default")
      (node (ref "R26") (pin "1") (pinfunction "1_1") (pintype "passive"))
      (node (ref "U3") (pin "66") (pinfunction "PA10_66") (pintype "bidirectional"))
    )
    (net (code "23") (name "/PA11") (class "Default")
      (node (ref "R28") (pin "1") (pinfunction "1_1") (pintype "passive"))
      (node (ref "U3") (pin "64") (pinfunction "PA11_64") (pintype "bidirectional"))
    )
    (net (code "24") (name "/PA12") (class "Default")
      (node (ref "R30") (pin "1") (pinfunction "1_1") (pintype "passive"))
      (node (ref "U3") (pin "68") (pinfunction "PA12_68") (pintype "bidirectional"))
    )
    (net (code "25") (name "/PA13") (class "Default")
      (node (ref "R32") (pin "1") (pinfunction "1_1") (pintype "passive"))
      (node (ref "U3") (pin "42") (pinfunction "PA13_42") (pintype "bidirectional"))
    )
    (net (code "26") (name "/PA14") (class "Default")
      (node (ref "R34") (pin "1") (pinfunction "1_1") (pintype "passive"))
      (node (ref "U3") (pin "51") (pinfunction "PA14_51") (pintype "bidirectional"))
    )
    (net (code "27") (name "/PA15") (class "Default")
      (node (ref "R36") (pin "1") (pinfunction "1_1") (pintype "passive"))
      (node (ref "U3") (pin "49") (pinfunction "PA15_49") (pintype "bidirectional"))
    )
    (net (code "28") (name "/PA16") (class "Default")
      (node (ref "R37") (pin "1") (pinfunction "1_1") (pintype "passive"))
      (node (ref "U3") (pin "45") (pinfunction "PA16_45") (pintype "bidirectional"))
    )
    (net (code "29") (name "/PA18") (class "Default")
      (node (ref "R151") (pin "1") (pinfunction "1_1") (pintype "passive"))
      (node (ref "U3") (pin "24") (pinfunction "PA18_24") (pintype "bidirectional"))
    )
    (net (code "30") (name "/PA19") (class "Default")
      (node (ref "C213") (pin "2") (pinfunction "2_2") (pintype "passive"))
      (node (ref "R143") (pin "1") (pinfunction "1_1") (pintype "passive"))
      (node (ref "U3") (pin "23") (pinfunction "PA19_23") (pintype "bidirectional"))
    )
    (net (code "31") (name "/PA20") (class "Default")
      (node (ref "C215") (pin "2") (pinfunction "2_2") (pintype "passive"))
      (node (ref "R150") (pin "1") (pinfunction "1_1") (pintype "passive"))
      (node (ref "U3") (pin "22") (pinfunction "PA20_22") (pintype "bidirectional"))
    )
    (net (code "32") (name "/PA21") (class "Default")
      (node (ref "C224") (pin "2") (pinfunction "2_2") (pintype "passive"))
      (node (ref "R631") (pin "1") (pinfunction "1_1") (pintype "passive"))
      (node (ref "U3") (pin "32") (pinfunction "PA21_32") (pintype "bidirectional"))
    )
    (net (code "33") (name "/PA22") (class "Default")
      (node (ref "R44") (pin "1") (pinfunction "1_1") (pintype "passive"))
      (node (ref "U3") (pin "37") (pinfunction "PA22_37") (pintype "bidirectional"))
    )
    (net (code "34") (name "/PA23") (class "Default")
      (node (ref "R46") (pin "1") (pinfunction "1_1") (pintype "passive"))
      (node (ref "U3") (pin "46") (pinfunction "PA23_46") (pintype "bidirectional"))
    )
    (net (code "35") (name "/PA24") (class "Default")
      (node (ref "R47") (pin "1") (pinfunction "1_1") (pintype "passive"))
      (node (ref "U3") (pin "56") (pinfunction "PA24_56") (pintype "bidirectional"))
    )
    (net (code "36") (name "/PA25") (class "Default")
      (node (ref "R48") (pin "1") (pinfunction "1_1") (pintype "passive"))
      (node (ref "U3") (pin "59") (pinfunction "PA25_59") (pintype "bidirectional"))
    )
    (net (code "37") (name "/PA26") (class "Default")
      (node (ref "R50") (pin "1") (pinfunction "1_1") (pintype "passive"))
      (node (ref "U3") (pin "62") (pinfunction "PA26_62") (pintype "bidirectional"))
    )
    (net (code "38") (name "/PA27") (class "Default")
      (node (ref "R52") (pin "1") (pinfunction "1_1") (pintype "passive"))
      (node (ref "U3") (pin "70") (pinfunction "PA27_70") (pintype "bidirectional"))
    )
    (net (code "39") (name "/PA28") (class "Default")
      (node (ref "R54") (pin "1") (pinfunction "1_1") (pintype "passive"))
      (node (ref "U3") (pin "112") (pinfunction "PA28_112") (pintype "bidirectional"))
    )
    (net (code "40") (name "/PA29") (class "Default")
      (node (ref "R56") (pin "1") (pinfunction "1_1") (pintype "passive"))
      (node (ref "U3") (pin "129") (pinfunction "PA29_129") (pintype "bidirectional"))
    )
    (net (code "41") (name "/PA30") (class "Default")
      (node (ref "R58") (pin "1") (pinfunction "1_1") (pintype "passive"))
      (node (ref "U3") (pin "116") (pinfunction "PA30_116") (pintype "bidirectional"))
    )
    (net (code "42") (name "/PA31") (class "Default")
      (node (ref "R59") (pin "1") (pinfunction "1_1") (pintype "passive"))
      (node (ref "U3") (pin "118") (pinfunction "PA31_118") (pintype "bidirectional"))
    )
    (net (code "43") (name "/PB00") (class "Default")
      (node (ref "C225") (pin "2") (pinfunction "2_2") (pintype "passive"))
      (node (ref "R73") (pin "2") (pinfunction "2_2") (pintype "passive"))
      (node (ref "U3") (pin "21") (pinfunction "PB00_21") (pintype "bidirectional"))
    )
    (net (code "44") (name "/PB01") (class "Default")
      (node (ref "C226") (pin "2") (pinfunction "2_2") (pintype "passive"))
      (node (ref "R75") (pin "2") (pinfunction "2_2") (pintype "passive"))
      (node (ref "U3") (pin "20") (pinfunction "PB01_20") (pintype "bidirectional"))
    )
    (net (code "45") (name "/PB02") (class "Default")
      (node (ref "C227") (pin "2") (pinfunction "2_2") (pintype "passive"))
      (node (ref "R77") (pin "2") (pinfunction "2_2") (pintype "passive"))
      (node (ref "U3") (pin "26") (pinfunction "PB02_26") (pintype "bidirectional"))
    )
    (net (code "46") (name "/PB03") (class "Default")
      (node (ref "C228") (pin "2") (pinfunction "2_2") (pintype "passive"))
      (node (ref "R79") (pin "2") (pinfunction "2_2") (pintype "passive"))
      (node (ref "U3") (pin "31") (pinfunction "PB03_31") (pintype "bidirectional"))
    )
    (net (code "47") (name "/PB04") (class "Default")
      (node (ref "R81") (pin "2") (pinfunction "2_2") (pintype "passive"))
      (node (ref "U3") (pin "105") (pinfunction "PB04_105") (pintype "bidirectional"))
    )
    (net (code "48") (name "/PB05") (class "Default")
      (node (ref "R83") (pin "2") (pinfunction "2_2") (pintype "passive"))
      (node (ref "R86") (pin "2") (pinfunction "2_2") (pintype "passive"))
      (node (ref "U3") (pin "109") (pinfunction "PB05_109") (pintype "bidirectional"))
    )
    (net (code "49") (name "/PB06") (class "Default")
      (node (ref "R85") (pin "2") (pinfunction "2_2") (pintype "passive"))
      (node (ref "U3") (pin "79") (pinfunction "PB06_79") (pintype "bidirectional"))
    )
    (net (code "50") (name "/PB07") (class "Default")
      (node (ref "R88") (pin "2") (pinfunction "2_2") (pintype "passive"))
      (node (ref "U3") (pin "89") (pinfunction "PB07_89") (pintype "bidirectional"))
    )
    (net (code "51") (name "/PB12") (class "Default")
      (node (ref "R94") (pin "2") (pinfunction "2_2") (pintype "passive"))
      (node (ref "U3") (pin "87") (pinfunction "PB12_87") (pintype "bidirectional"))
    )
    (net (code "52") (name "/PB13") (class "Default")
      (node (ref "R621") (pin "2") (pinfunction "2_2") (pintype "passive"))
      (node (ref "U3") (pin "144") (pinfunction "PB13_144") (pintype "bidirectional"))
    )
    (net (code "53") (name "/PC00") (class "Default")
      (node (ref "C217") (pin "2") (pinfunction "2_2") (pintype "passive"))
      (node (ref "R278") (pin "1") (pinfunction "1_1") (pintype "passive"))
      (node (ref "U3") (pin "11") (pinfunction "PC00_11") (pintype "bidirectional"))
    )
    (net (code "54") (name "/PC01") (class "Default")
      (node (ref "R64") (pin "1") (pinfunction "1_1") (pintype "passive"))
      (node (ref "U3") (pin "38") (pinfunction "PC01_38") (pintype "bidirectional"))
    )
    (net (code "55") (name "/PC02") (class "Default")
      (node (ref "R66") (pin "1") (pinfunction "1_1") (pintype "passive"))
      (node (ref "U3") (pin "39") (pinfunction "PC02_39") (pintype "bidirectional"))
    )
    (net (code "56") (name "/PC03") (class "Default")
      (node (ref "R68") (pin "1") (pinfunction "1_1") (pintype "passive"))
      (node (ref "U3") (pin "40") (pinfunction "PC03_40") (pintype "bidirectional"))
    )
    (net (code "57") (name "/PC04") (class "Default")
      (node (ref "R69") (pin "1") (pinfunction "1_1") (pintype "passive"))
      (node (ref "U3") (pin "41") (pinfunction "PC04_41") (pintype "bidirectional"))
    )
    (net (code "58") (name "/PC05") (class "Default")
      (node (ref "R70") (pin "1") (pinfunction "1_1") (pintype "passive"))
      (node (ref "U3") (pin "58") (pinfunction "PC05_58") (pintype "bidirectional"))
    )
    (net (code "59") (name "/PC06") (class "Default")
      (node (ref "R71") (pin "1") (pinfunction "1_1") (pintype "passive"))
      (node (ref "U3") (pin "54") (pinfunction "PC06_54") (pintype "bidirectional"))
    )
    (net (code "60") (name "/PC07") (class "Default")
      (node (ref "R72") (pin "1") (pinfunction "1_1") (pintype "passive"))
      (node (ref "U3") (pin "48") (pinfunction "PC07_48") (pintype "bidirectional"))
    )
    (net (code "61") (name "/PC08") (class "Default")
      (node (ref "R74") (pin "1") (pinfunction "1_1") (pintype "passive"))
      (node (ref "U3") (pin "82") (pinfunction "PC08_82") (pintype "bidirectional"))
    )
    (net (code "62") (name "/PC09") (class "Default")
      (node (ref "R76") (pin "1") (pinfunction "1_1") (pintype "passive"))
      (node (ref "U3") (pin "86") (pinfunction "PC09_86") (pintype "bidirectional"))
    )
    (net (code "63") (name "/PC10") (class "Default")
      (node (ref "R78") (pin "1") (pinfunction "1_1") (pintype "passive"))
      (node (ref "U3") (pin "90") (pinfunction "PC10_90") (pintype "bidirectional"))
    )
    (net (code "64") (name "/PC11") (class "Default")
      (node (ref "R80") (pin "1") (pinfunction "1_1") (pintype "passive"))
      (node (ref "U3") (pin "94") (pinfunction "PC11_94") (pintype "bidirectional"))
    )
    (net (code "65") (name "/PC12") (class "Default")
      (node (ref "R82") (pin "1") (pinfunction "1_1") (pintype "passive"))
      (node (ref "U3") (pin "17") (pinfunction "PC12_17") (pintype "bidirectional"))
    )
    (net (code "66") (name "/PC13") (class "Default")
      (node (ref "C218") (pin "2") (pinfunction "2_2") (pintype "passive"))
      (node (ref "R84") (pin "1") (pinfunction "1_1") (pintype "passive"))
      (node (ref "U3") (pin "19") (pinfunction "PC13_19") (pintype "bidirectional"))
    )
    (net (code "67") (name "/PC14") (class "Default")
      (node (ref "R87") (pin "1") (pinfunction "1_1") (pintype "passive"))
      (node (ref "U3") (pin "97") (pinfunction "PC14_97") (pintype "bidirectional"))
    )
    (net (code "68") (name "/PC15") (class "Default")
      (node (ref "C219") (pin "2") (pinfunction "2_2") (pintype "passive"))
      (node (ref "R89") (pin "1") (pinfunction "1_1") (pintype "passive"))
      (node (ref "U3") (pin "18") (pinfunction "PC15_18") (pintype "bidirectional"))
    )
    (net (code "69") (name "/PC16") (class "Default")
      (node (ref "R91") (pin "1") (pinfunction "1_1") (pintype "passive"))
      (node (ref "U3") (pin "100") (pinfunction "PC16_100") (pintype "bidirectional"))
    )
    (net (code "70") (name "/PC17") (class "Default")
      (node (ref "R93") (pin "1") (pinfunction "1_1") (pintype "passive"))
      (node (ref "U3") (pin "103") (pinfunction "PC17_103") (pintype "bidirectional"))
    )
    (net (code "71") (name "/PC18") (class "Default")
      (node (ref "R95") (pin "1") (pinfunction "1_1") (pintype "passive"))
      (node (ref "U3") (pin "111") (pinfunction "PC18_111") (pintype "bidirectional"))
    )
    (net (code "72") (name "/PC19") (class "Default")
      (node (ref "R622") (pin "1") (pinfunction "1_1") (pintype "passive"))
      (node (ref "U3") (pin "117") (pinfunction "PC19_117") (pintype "bidirectional"))
    )
    (net (code "73") (name "/PC20") (class "Default")
      (node (ref "R98") (pin "1") (pinfunction "1_1") (pintype "passive"))
      (node (ref "U3") (pin "120") (pinfunction "PC20_120") (pintype "bidirectional"))
    )
    (net (code "74") (name "/PC21") (class "Default")
      (node (ref "R99") (pin "1") (pinfunction "1_1") (pintype "passive"))
      (node (ref "U3") (pin "122") (pinfunction "PC21_122") (pintype "bidirectional"))
    )
    (net (code "75") (name "/PC22") (class "Default")
      (node (ref "R100") (pin "1") (pinfunction "1_1") (pintype "passive"))
      (node (ref "U3") (pin "124") (pinfunction "PC22_124") (pintype "bidirectional"))
    )
    (net (code "76") (name "/PC23") (class "Default")
      (node (ref "R101") (pin "1") (pinfunction "1_1") (pintype "passive"))
      (node (ref "U3") (pin "127") (pinfunction "PC23_127") (pintype "bidirectional"))
    )
    (net (code "77") (name "/PC24") (class "Default")
      (node (ref "R102") (pin "1") (pinfunction "1_1") (pintype "passive"))
      (node (ref "U3") (pin "130") (pinfunction "PC24_130") (pintype "bidirectional"))
    )
    (net (code "78") (name "/PC25") (class "Default")
      (node (ref "R286") (pin "1") (pinfunction "1_1") (pintype "passive"))
      (node (ref "U3") (pin "133") (pinfunction "PC25_133") (pintype "bidirectional"))
    )
    (net (code "79") (name "/PC26") (class "Default")
      (node (ref "R103") (pin "1") (pinfunction "1_1") (pintype "passive"))
      (node (ref "U3") (pin "13") (pinfunction "PC26_13") (pintype "bidirectional"))
    )
    (net (code "80") (name "/PC27") (class "Default")
      (node (ref "R104") (pin "1") (pinfunction "1_1") (pintype "passive"))
      (node (ref "U3") (pin "12") (pinfunction "PC27_12") (pintype "bidirectional"))
    )
    (net (code "81") (name "/PC28") (class "Default")
      (node (ref "R105") (pin "1") (pinfunction "1_1") (pintype "passive"))
      (node (ref "U3") (pin "76") (pinfunction "PC28_76") (pintype "bidirectional"))
    )
    (net (code "82") (name "/PC29") (class "Default")
      (node (ref "C220") (pin "2") (pinfunction "2_2") (pintype "passive"))
      (node (ref "R106") (pin "1") (pinfunction "1_1") (pintype "passive"))
      (node (ref "U3") (pin "16") (pinfunction "PC29_16") (pintype "bidirectional"))
    )
    (net (code "83") (name "/PC30") (class "Default")
      (node (ref "C221") (pin "2") (pinfunction "2_2") (pintype "passive"))
      (node (ref "R107") (pin "1") (pinfunction "1_1") (pintype "passive"))
      (node (ref "U3") (pin "15") (pinfunction "PC30_15") (pintype "bidirectional"))
    )
    (net (code "84") (name "/PC31") (class "Default")
      (node (ref "C223") (pin "2") (pinfunction "2_2") (pintype "passive"))
      (node (ref "R108") (pin "1") (pinfunction "1_1") (pintype "passive"))
      (node (ref "U3") (pin "14") (pinfunction "PC31_14") (pintype "bidirectional"))
    )
    (net (code "85") (name "/PD00") (class "Default")
      (node (ref "R12") (pin "2") (pinfunction "2_2") (pintype "passive"))
      (node (ref "U3") (pin "1") (pinfunction "PD00_1") (pintype "bidirectional"))
    )
    (net (code "86") (name "/PD01") (class "Default")
      (node (ref "R613") (pin "2") (pinfunction "2_2") (pintype "passive"))
      (node (ref "U3") (pin "132") (pinfunction "PD01_132") (pintype "bidirectional"))
    )
    (net (code "87") (name "/PD02") (class "Default")
      (node (ref "R16") (pin "2") (pinfunction "2_2") (pintype "passive"))
      (node (ref "U3") (pin "131") (pinfunction "PD02_131") (pintype "bidirectional"))
    )
    (net (code "88") (name "/PD03") (class "Default")
      (node (ref "R18") (pin "2") (pinfunction "2_2") (pintype "passive"))
      (node (ref "U3") (pin "128") (pinfunction "PD03_128") (pintype "bidirectional"))
    )
    (net (code "89") (name "/PD04") (class "Default")
      (node (ref "R19") (pin "2") (pinfunction "2_2") (pintype "passive"))
      (node (ref "U3") (pin "126") (pinfunction "PD04_126") (pintype "bidirectional"))
    )
    (net (code "90") (name "/PD05") (class "Default")
      (node (ref "R21") (pin "2") (pinfunction "2_2") (pintype "passive"))
      (node (ref "U3") (pin "125") (pinfunction "PD05_125") (pintype "bidirectional"))
    )
    (net (code "91") (name "/PD06") (class "Default")
      (node (ref "R23") (pin "2") (pinfunction "2_2") (pintype "passive"))
      (node (ref "U3") (pin "121") (pinfunction "PD06_121") (pintype "bidirectional"))
    )
    (net (code "92") (name "/PD07") (class "Default")
      (node (ref "R616") (pin "2") (pinfunction "2_2") (pintype "passive"))
      (node (ref "U3") (pin "119") (pinfunction "PD07_119") (pintype "bidirectional"))
    )
    (net (code "93") (name "/PD08") (class "Default")
      (node (ref "R312") (pin "2") (pinfunction "2_2") (pintype "passive"))
      (node (ref "U3") (pin "113") (pinfunction "PD08_113") (pintype "bidirectional"))
    )
    (net (code "94") (name "/PD09") (class "Default")
      (node (ref "R25") (pin "2") (pinfunction "2_2") (pintype "passive"))
      (node (ref "U3") (pin "110") (pinfunction "PD09_110") (pintype "bidirectional"))
    )
    (net (code "95") (name "/PD10") (class "Default")
      (node (ref "R27") (pin "2") (pinfunction "2_2") (pintype "passive"))
      (node (ref "U3") (pin "101") (pinfunction "PD10_101") (pintype "bidirectional"))
    )
    (net (code "96") (name "/PD11") (class "Default")
      (node (ref "R29") (pin "2") (pinfunction "2_2") (pintype "passive"))
      (node (ref "U3") (pin "98") (pinfunction "PD11_98") (pintype "bidirectional"))
    )
    (net (code "97") (name "/PD12") (class "Default")
      (node (ref "R31") (pin "2") (pinfunction "2_2") (pintype "passive"))
      (node (ref "U3") (pin "92") (pinfunction "PD12_92") (pintype "bidirectional"))
    )
    (net (code "98") (name "/PD13") (class "Default")
      (node (ref "R33") (pin "2") (pinfunction "2_2") (pintype "passive"))
      (node (ref "U3") (pin "88") (pinfunction "PD13_88") (pintype "bidirectional"))
    )
    (net (code "99") (name "/PD14") (class "Default")
      (node (ref "R617") (pin "2") (pinfunction "2_2") (pintype "passive"))
      (node (ref "U3") (pin "84") (pinfunction "PD14_84") (pintype "bidirectional"))
    )
    (net (code "100") (name "/PD15") (class "Default")
      (node (ref "R131") (pin "2") (pinfunction "2_2") (pintype "passive"))
      (node (ref "U3") (pin "106") (pinfunction "PD15_106") (pintype "bidirectional"))
    )
    (net (code "101") (name "/PD16") (class "Default")
      (node (ref "R133") (pin "2") (pinfunction "2_2") (pintype "passive"))
      (node (ref "U3") (pin "78") (pinfunction "PD16_78") (pintype "bidirectional"))
    )
    (net (code "102") (name "/PD17") (class "Default")
      (node (ref "R39") (pin "2") (pinfunction "2_2") (pintype "passive"))
      (node (ref "U3") (pin "74") (pinfunction "PD17_74") (pintype "bidirectional"))
    )
    (net (code "103") (name "/PD18") (class "Default")
      (node (ref "R618") (pin "2") (pinfunction "2_2") (pintype "passive"))
      (node (ref "U3") (pin "69") (pinfunction "PD18_69") (pintype "bidirectional"))
    )
    (net (code "104") (name "/PD19") (class "Default")
      (node (ref "R41") (pin "1") (pinfunction "1_1") (pintype "passive"))
      (node (ref "U3") (pin "67") (pinfunction "PD19_67") (pintype "bidirectional"))
    )
    (net (code "105") (name "/PD20") (class "Default")
      (node (ref "R42") (pin "2") (pinfunction "2_2") (pintype "passive"))
      (node (ref "U3") (pin "65") (pinfunction "PD20_65") (pintype "bidirectional"))
    )
    (net (code "106") (name "/PD21") (class "Default")
      (node (ref "R43") (pin "2") (pinfunction "2_2") (pintype "passive"))
      (node (ref "U3") (pin "63") (pinfunction "PD21_63") (pintype "bidirectional"))
    )
    (net (code "107") (name "/PD22") (class "Default")
      (node (ref "R45") (pin "2") (pinfunction "2_2") (pintype "passive"))
      (node (ref "U3") (pin "60") (pinfunction "PD22_60") (pintype "bidirectional"))
    )
    (net (code "108") (name "/PD23") (class "Default")
      (node (ref "R126") (pin "2") (pinfunction "2_2") (pintype "passive"))
      (node (ref "U3") (pin "57") (pinfunction "PD23_57") (pintype "bidirectional"))
    )
    (net (code "109") (name "/PD24") (class "Default")
      (node (ref "R127") (pin "2") (pinfunction "2_2") (pintype "passive"))
      (node (ref "U3") (pin "55") (pinfunction "PD24_55") (pintype "bidirectional"))
    )
    (net (code "110") (name "/PD25") (class "Default")
      (node (ref "R49") (pin "2") (pinfunction "2_2") (pintype "passive"))
      (node (ref "U3") (pin "52") (pinfunction "PD25_52") (pintype "bidirectional"))
    )
    (net (code "111") (name "/PD26") (class "Default")
      (node (ref "R51") (pin "2") (pinfunction "2_2") (pintype "passive"))
      (node (ref "U3") (pin "53") (pinfunction "PD26_53") (pintype "bidirectional"))
    )
    (net (code "112") (name "/PD27") (class "Default")
      (node (ref "R53") (pin "2") (pinfunction "2_2") (pintype "passive"))
      (node (ref "U3") (pin "47") (pinfunction "PD27_47") (pintype "bidirectional"))
    )
    (net (code "113") (name "/PD28") (class "Default")
      (node (ref "R55") (pin "2") (pinfunction "2_2") (pintype "passive"))
      (node (ref "U3") (pin "71") (pinfunction "PD28_71") (pintype "bidirectional"))
    )
    (net (code "114") (name "/PD29") (class "Default")
      (node (ref "R57") (pin "1") (pinfunction "1_1") (pintype "passive"))
      (node (ref "U3") (pin "108") (pinfunction "PD29_108") (pintype "bidirectional"))
    )
    (net (code "115") (name "/PD30") (class "Default")
      (node (ref "R277") (pin "1") (pinfunction "1_1") (pintype "passive"))
      (node (ref "U3") (pin "34") (pinfunction "PD30_34") (pintype "bidirectional"))
    )
    (net (code "116") (name "/PD31") (class "Default")
      (node (ref "R650") (pin "1") (pinfunction "1_1") (pintype "passive"))
      (node (ref "U3") (pin "2") (pinfunction "PD31_2") (pintype "bidirectional"))
    )
    (net (code "117") (name "/PE00") (class "Default")
      (node (ref "R619") (pin "2") (pinfunction "2_2") (pintype "passive"))
      (node (ref "U3") (pin "4") (pinfunction "PE00_4") (pintype "bidirectional"))
    )
    (net (code "118") (name "/PE01") (class "Default")
      (node (ref "R65") (pin "2") (pinfunction "2_2") (pintype "passive"))
      (node (ref "U3") (pin "6") (pinfunction "PE01_6") (pintype "bidirectional"))
    )
    (net (code "119") (name "/PE02") (class "Default")
      (node (ref "R67") (pin "2") (pinfunction "2_2") (pintype "passive"))
      (node (ref "U3") (pin "7") (pinfunction "PE02_7") (pintype "bidirectional"))
    )
    (net (code "120") (name "/PE03") (class "Default")
      (node (ref "R281") (pin "2") (pinfunction "2_2") (pintype "passive"))
      (node (ref "U3") (pin "10") (pinfunction "PE03_10") (pintype "bidirectional"))
    )
    (net (code "121") (name "/PE04") (class "Default")
      (node (ref "R282") (pin "2") (pinfunction "2_2") (pintype "passive"))
      (node (ref "U3") (pin "27") (pinfunction "PE04_27") (pintype "bidirectional"))
    )
    (net (code "122") (name "/PE05") (class "Default")
      (node (ref "R620") (pin "2") (pinfunction "2_2") (pintype "passive"))
      (node (ref "U3") (pin "28") (pinfunction "PE05_28") (pintype "bidirectional"))
    )
    (net (code "123") (name "/nSTART") (class "Default")
      (node (ref "R107") (pin "2") (pinfunction "2_2") (pintype "passive"))
    )
    (net (code "124") (name "3.3V_MCU") (class "Default")
      (node (ref "C21") (pin "1") (pinfunction "1_1") (pintype "passive"))
      (node (ref "C23") (pin "2") (pinfunction "2_2") (pintype "passive"))
      (node (ref "C24") (pin "2") (pinfunction "2_2") (pintype "passive"))
      (node (ref "C25") (pin "2") (pinfunction "2_2") (pintype "passive"))
      (node (ref "C26") (pin "2") (pinfunction "2_2") (pintype "passive"))
      (node (ref "C27") (pin "2") (pinfunction "2_2") (pintype "passive"))
      (node (ref "C28") (pin "2") (pinfunction "2_2") (pintype "passive"))
      (node (ref "C29") (pin "2") (pinfunction "2_2") (pintype "passive"))
      (node (ref "C30") (pin "2") (pinfunction "2_2") (pintype "passive"))
      (node (ref "C31") (pin "2") (pinfunction "2_2") (pintype "passive"))
      (node (ref "J3") (pin "2") (pinfunction "2_2") (pintype "passive"))
      (node (ref "R141") (pin "1") (pinfunction "1_1") (pintype "passive"))
      (node (ref "R285") (pin "1") (pinfunction "1_1") (pintype "passive"))
      (node (ref "R61") (pin "2") (pinfunction "2_2") (pintype "passive"))
      (node (ref "U3") (pin "134") (pinfunction "VDDUTMII_134") (pintype "power_in"))
      (node (ref "U3") (pin "143") (pinfunction "VDDPLLUSB_143") (pintype "power_in"))
      (node (ref "U3") (pin "30") (pinfunction "VDDIO_30") (pintype "power_in"))
      (node (ref "U3") (pin "43") (pinfunction "VDDIO_43") (pintype "power_in"))
      (node (ref "U3") (pin "5") (pinfunction "VDDIN_5") (pintype "power_in"))
      (node (ref "U3") (pin "72") (pinfunction "VDDIO_72") (pintype "power_in"))
      (node (ref "U3") (pin "80") (pinfunction "VDDIO_80") (pintype "power_in"))
      (node (ref "U3") (pin "9") (pinfunction "ADVREFP_9") (pintype "power_in"))
      (node (ref "U3") (pin "96") (pinfunction "VDDIO_96") (pintype "power_in"))
    )
    (net (code "125") (name "ADC_SWITCH") (class "Default")
      (node (ref "R79") (pin "1") (pinfunction "1_1") (pintype "passive"))
    )
    (net (code "126") (name "ADC_TEMP1") (class "Default")
      (node (ref "R143") (pin "2") (pinfunction "2_2") (pintype "passive"))
    )
    (net (code "127") (name "ADC_TEMP2") (class "Default")
      (node (ref "R150") (pin "2") (pinfunction "2_2") (pintype "passive"))
    )
    (net (code "128") (name "ADC_TEMP3") (class "Default")
      (node (ref "R108") (pin "2") (pinfunction "2_2") (pintype "passive"))
    )
    (net (code "129") (name "ADC_TEMP4") (class "Default")
      (node (ref "R75") (pin "1") (pinfunction "1_1") (pintype "passive"))
    )
    (net (code "130") (name "ADC_TEMP5") (class "Default")
      (node (ref "R89") (pin "2") (pinfunction "2_2") (pintype "passive"))
    )
    (net (code "131") (name "ADC_TEMP6") (class "Default")
      (node (ref "R84") (pin "2") (pinfunction "2_2") (pintype "passive"))
    )
    (net (code "132") (name "ADC_TEMP7") (class "Default")
      (node (ref "R278") (pin "2") (pinfunction "2_2") (pintype "passive"))
    )
    (net (code "133") (name "ADC_TEMP8") (class "Default")
      (node (ref "R106") (pin "2") (pinfunction "2_2") (pintype "passive"))
    )
    (net (code "134") (name "ADC_TEMP_SENSOR") (class "Default")
      (node (ref "R281") (pin "1") (pinfunction "1_1") (pintype "passive"))
    )
    (net (code "135") (name "ADT2_USB_D_N") (class "Default")
      (node (ref "U3") (pin "136") (pinfunction "HSDM_136") (pintype "bidirectional"))
    )
    (net (code "136") (name "ADT2_USB_D_P") (class "Default")
      (node (ref "U3") (pin "137") (pinfunction "HSDP_137") (pintype "bidirectional"))
    )
    (net (code "137") (name "CANRX1") (class "Default")
      (node (ref "R82") (pin "2") (pinfunction "2_2") (pintype "passive"))
    )
    (net (code "138") (name "CANTX1") (class "Default")
      (node (ref "R87") (pin "2") (pinfunction "2_2") (pintype "passive"))
    )
    (net (code "139") (name "CPU_MCU_SPI_CS") (class "Default")
      (node (ref "R286") (pin "2") (pinfunction "2_2") (pintype "passive"))
    )
    (net (code "140") (name "GND") (class "Default")
      (node (ref "C15") (pin "1") (pinfunction "1_1") (pintype "passive"))
      (node (ref "C18") (pin "1") (pinfunction "1_1") (pintype "passive"))
      (node (ref "C19") (pin "1") (pinfunction "1_1") (pintype "passive"))
      (node (ref "C20") (pin "1") (pinfunction "1_1") (pintype "passive"))
      (node (ref "C21") (pin "2") (pinfunction "2_2") (pintype "passive"))
      (node (ref "C213") (pin "1") (pinfunction "1_1") (pintype "passive"))
      (node (ref "C215") (pin "1") (pinfunction "1_1") (pintype "passive"))
      (node (ref "C217") (pin "1") (pinfunction "1_1") (pintype "passive"))
      (node (ref "C218") (pin "1") (pinfunction "1_1") (pintype "passive"))
      (node (ref "C219") (pin "1") (pinfunction "1_1") (pintype "passive"))
      (node (ref "C22") (pin "2") (pinfunction "2_2") (pintype "passive"))
      (node (ref "C220") (pin "1") (pinfunction "1_1") (pintype "passive"))
      (node (ref "C221") (pin "1") (pinfunction "1_1") (pintype "passive"))
      (node (ref "C223") (pin "1") (pinfunction "1_1") (pintype "passive"))
      (node (ref "C224") (pin "1") (pinfunction "1_1") (pintype "passive"))
      (node (ref "C225") (pin "1") (pinfunction "1_1") (pintype "passive"))
      (node (ref "C226") (pin "1") (pinfunction "1_1") (pintype "passive"))
      (node (ref "C227") (pin "1") (pinfunction "1_1") (pintype "passive"))
      (node (ref "C228") (pin "1") (pinfunction "1_1") (pintype "passive"))
      (node (ref "C23") (pin "1") (pinfunction "1_1") (pintype "passive"))
      (node (ref "C24") (pin "1") (pinfunction "1_1") (pintype "passive"))
      (node (ref "C25") (pin "1") (pinfunction "1_1") (pintype "passive"))
      (node (ref "C26") (pin "1") (pinfunction "1_1") (pintype "passive"))
      (node (ref "C27") (pin "1") (pinfunction "1_1") (pintype "passive"))
      (node (ref "C28") (pin "1") (pinfunction "1_1") (pintype "passive"))
      (node (ref "C29") (pin "1") (pinfunction "1_1") (pintype "passive"))
      (node (ref "C30") (pin "1") (pinfunction "1_1") (pintype "passive"))
      (node (ref "C31") (pin "1") (pinfunction "1_1") (pintype "passive"))
      (node (ref "C32") (pin "1") (pinfunction "1_1") (pintype "passive"))
      (node (ref "C33") (pin "1") (pinfunction "1_1") (pintype "passive"))
      (node (ref "C34") (pin "1") (pinfunction "1_1") (pintype "passive"))
      (node (ref "C35") (pin "1") (pinfunction "1_1") (pintype "passive"))
      (node (ref "C36") (pin "1") (pinfunction "1_1") (pintype "passive"))
      (node (ref "C37") (pin "1") (pinfunction "1_1") (pintype "passive"))
      (node (ref "C38") (pin "1") (pinfunction "1_1") (pintype "passive"))
      (node (ref "C39") (pin "1") (pinfunction "1_1") (pintype "passive"))
      (node (ref "J3") (pin "3") (pinfunction "3_3") (pintype "passive"))
      (node (ref "R110") (pin "1") (pinfunction "1_1") (pintype "passive"))
      (node (ref "R298") (pin "2") (pinfunction "2_2") (pintype "passive"))
      (node (ref "R659") (pin "2") (pinfunction "2_2") (pintype "passive"))
      (node (ref "U3") (pin "115") (pinfunction "GND_115") (pintype "power_in"))
      (node (ref "U3") (pin "135") (pinfunction "GND_135") (pintype "power_in"))
      (node (ref "U3") (pin "138") (pinfunction "GND_138") (pintype "power_in"))
      (node (ref "U3") (pin "44") (pinfunction "GND_44") (pintype "power_in"))
      (node (ref "U3") (pin "61") (pinfunction "GND_61") (pintype "power_in"))
      (node (ref "U3") (pin "8") (pinfunction "ADVREFN_8") (pintype "power_in"))
      (node (ref "U3") (pin "95") (pinfunction "GND_95") (pintype "power_in"))
      (node (ref "XC2") (pin "2") (pinfunction "2_2") (pintype "passive"))
      (node (ref "XC2") (pin "4") (pinfunction "4_4") (pintype "passive"))
    )
    (net (code "141") (name "HEATER_PWM_1") (class "Default")
      (node (ref "R52") (pin "2") (pinfunction "2_2") (pintype "passive"))
    )
    (net (code "142") (name "HEATER_PWM_2") (class "Default")
      (node (ref "R11") (pin "2") (pinfunction "2_2") (pintype "passive"))
    )
    (net (code "143") (name "HEATER_PWM_3") (class "Default")
      (node (ref "R13") (pin "2") (pinfunction "2_2") (pintype "passive"))
    )
    (net (code "144") (name "HEATER_PWM_4") (class "Default")
      (node (ref "R50") (pin "2") (pinfunction "2_2") (pintype "passive"))
    )
    (net (code "145") (name "HEATER_PWM_5") (class "Default")
      (node (ref "R74") (pin "2") (pinfunction "2_2") (pintype "passive"))
    )
    (net (code "146") (name "HEATER_PWM_6") (class "Default")
      (node (ref "R101") (pin "2") (pinfunction "2_2") (pintype "passive"))
    )
    (net (code "147") (name "HEATER_PWM_7") (class "Default")
      (node (ref "R70") (pin "2") (pinfunction "2_2") (pintype "passive"))
    )
    (net (code "148") (name "HEATER_PWM_8") (class "Default")
      (node (ref "R71") (pin "2") (pinfunction "2_2") (pintype "passive"))
    )
    (net (code "149") (name "IF_MCU_SHUTDOWN") (class "Default")
      (node (ref "R312") (pin "1") (pinfunction "1_1") (pintype "passive"))
    )
    (net (code "150") (name "LASER_ADC_1") (class "Default")
      (node (ref "R73") (pin "1") (pinfunction "1_1") (pintype "passive"))
    )
    (net (code "151") (name "LASER_ADC_2") (class "Default")
      (node (ref "R77") (pin "1") (pinfunction "1_1") (pintype "passive"))
    )
    (net (code "153") (name "LASER_DAC_LATCH") (class "Default")
      (node (ref "R91") (pin "2") (pinfunction "2_2") (pintype "passive"))
    )
    (net (code "154") (name "LASER_SPI_nCS1") (class "Default")
      (node (ref "R59") (pin "2") (pinfunction "2_2") (pintype "passive"))
    )
    (net (code "155") (name "LASER_SW_EXT_CS") (class "Default")
      (node (ref "R37") (pin "2") (pinfunction "2_2") (pintype "passive"))
    )
    (net (code "156") (name "LASER_SW_INT_CS") (class "Default")
      (node (ref "R72") (pin "2") (pinfunction "2_2") (pintype "passive"))
    )
    (net (code "157") (name "LSM6DSOX_INT") (class "Default")
      (node (ref "R99") (pin "2") (pinfunction "2_2") (pintype "passive"))
    )
    (net (code "158") (name "MCU_CONSOLE_RX") (class "Default")
      (node (ref "R49") (pin "1") (pinfunction "1_1") (pintype "passive"))
    )
    (net (code "159") (name "MCU_CONSOLE_TX") (class "Default")
      (node (ref "R51") (pin "1") (pinfunction "1_1") (pintype "passive"))
    )
    (net (code "160") (name "MCU_FRAM_nCS") (class "Default")
      (node (ref "R41") (pin "2") (pinfunction "2_2") (pintype "passive"))
    )
    (net (code "161") (name "MCU_HD4_I2C2_SCL") (class "Default")
      (node (ref "R55") (pin "1") (pinfunction "1_1") (pintype "passive"))
    )
    (net (code "162") (name "MCU_HD4_I2C2_SDA") (class "Default")
      (node (ref "R53") (pin "1") (pinfunction "1_1") (pintype "passive"))
    )
    (net (code "163") (name "MCU_HD4_I2C_EN") (class "Default")
      (node (ref "R93") (pin "2") (pinfunction "2_2") (pintype "passive"))
    )
    (net (code "164") (name "MCU_I2C0_SCL") (class "Default")
      (node (ref "R20") (pin "2") (pinfunction "2_2") (pintype "passive"))
    )
    (net (code "165") (name "MCU_I2C0_SDA") (class "Default")
      (node (ref "R17") (pin "2") (pinfunction "2_2") (pintype "passive"))
    )
    (net (code "166") (name "MCU_I2C1_SCL") (class "Default")
      (node (ref "R86") (pin "1") (pinfunction "1_1") (pintype "passive"))
    )
    (net (code "167") (name "MCU_I2C1_SDA") (class "Default")
      (node (ref "R81") (pin "1") (pinfunction "1_1") (pintype "passive"))
    )
    (net (code "168") (name "MCU_LASER_QSPI_MISO") (class "Default")
      (node (ref "R524") (pin "2") (pinfunction "2_2") (pintype "passive"))
    )
    (net (code "169") (name "MCU_LASER_QSPI_MOSI") (class "Default")
      (node (ref "R458") (pin "2") (pinfunction "2_2") (pintype "passive"))
    )
    (net (code "170") (name "MCU_LASER_QSPI_SCK") (class "Default")
      (node (ref "R632") (pin "2") (pinfunction "2_2") (pintype "passive"))
    )
    (net (code "171") (name "MCU_MRAM_QSPI_CLK") (class "Default")
      (node (ref "R34") (pin "2") (pinfunction "2_2") (pintype "passive"))
      (node (ref "R632") (pin "1") (pinfunction "1_1") (pintype "passive"))
    )
    (net (code "172") (name "MCU_MRAM_QSPI_IO0") (class "Default")
      (node (ref "R32") (pin "2") (pinfunction "2_2") (pintype "passive"))
      (node (ref "R458") (pin "1") (pinfunction "1_1") (pintype "passive"))
    )
    (net (code "173") (name "MCU_MRAM_QSPI_IO1") (class "Default")
      (node (ref "R30") (pin "2") (pinfunction "2_2") (pintype "passive"))
      (node (ref "R524") (pin "1") (pinfunction "1_1") (pintype "passive"))
    )
    (net (code "174") (name "MCU_PRAM_SPI1_nCS") (class "Default")
      (node (ref "R105") (pin "2") (pinfunction "2_2") (pintype "passive"))
    )
    (net (code "175") (name "MCU_PRAM_SW_SEL") (class "Default")
      (node (ref "R457") (pin "2") (pinfunction "2_2") (pintype "passive"))
    )
    (net (code "176") (name "MCU_RAM_QSPI_nCS") (class "Default")
      (node (ref "R28") (pin "2") (pinfunction "2_2") (pintype "passive"))
    )
    (net (code "177") (name "MCU_RTC_CLKOUT") (class "Default")
      (node (ref "R68") (pin "2") (pinfunction "2_2") (pintype "passive"))
    )
    (net (code "178") (name "MCU_RTC_INT") (class "Default")
      (node (ref "R69") (pin "2") (pinfunction "2_2") (pintype "passive"))
    )
    (net (code "179") (name "MCU_SENSOR1_nIRQ") (class "Default")
      (node (ref "R126") (pin "1") (pinfunction "1_1") (pintype "passive"))
    )
    (net (code "180") (name "MCU_SENSOR2_nIRQ") (class "Default")
      (node (ref "R127") (pin "1") (pinfunction "1_1") (pintype "passive"))
    )
    (net (code "181") (name "MCU_SENSOR3_nIRQ") (class "Default")
      (node (ref "R57") (pin "2") (pinfunction "2_2") (pintype "passive"))
    )
    (net (code "182") (name "MCU_SENSOR4_nIRQ") (class "Default")
      (node (ref "R277") (pin "2") (pinfunction "2_2") (pintype "passive"))
    )
    (net (code "183") (name "MCU_SOM_GPIO_A") (class "Default")
      (node (ref "R25") (pin "1") (pinfunction "1_1") (pintype "passive"))
    )
    (net (code "184") (name "MCU_SOM_GPIO_B") (class "Default")
      (node (ref "R27") (pin "1") (pinfunction "1_1") (pintype "passive"))
    )
    (net (code "185") (name "MCU_SPI0_CMD_SOLE_A") (class "Default")
      (node (ref "R622") (pin "2") (pinfunction "2_2") (pintype "passive"))
    )
    (net (code "186") (name "MCU_SPI0_CMD_SOLE_B") (class "Default")
      (node (ref "R620") (pin "1") (pinfunction "1_1") (pintype "passive"))
    )
    (net (code "187") (name "MCU_SPI0_CMD_SOLE_C") (class "Default")
      (node (ref "R617") (pin "1") (pinfunction "1_1") (pintype "passive"))
    )
    (net (code "188") (name "MCU_SPI0_CMD_SOLE_D") (class "Default")
      (node (ref "R616") (pin "1") (pinfunction "1_1") (pintype "passive"))
    )
    (net (code "189") (name "MCU_SPI0_CMD_SOLE_E") (class "Default")
      (node (ref "R615") (pin "2") (pinfunction "2_2") (pintype "passive"))
    )
    (net (code "190") (name "MCU_SPI0_MISO") (class "Default")
      (node (ref "R141") (pin "2") (pinfunction "2_2") (pintype "passive"))
      (node (ref "R42") (pin "1") (pinfunction "1_1") (pintype "passive"))
    )
    (net (code "191") (name "MCU_SPI0_MOSI") (class "Default")
      (node (ref "R43") (pin "1") (pinfunction "1_1") (pintype "passive"))
    )
    (net (code "192") (name "MCU_SPI0_SCK") (class "Default")
      (node (ref "R45") (pin "1") (pinfunction "1_1") (pintype "passive"))
    )
    (net (code "193") (name "MCU_SPI0_nCS_SOLE_A") (class "Default")
      (node (ref "R621") (pin "1") (pinfunction "1_1") (pintype "passive"))
    )
    (net (code "194") (name "MCU_SPI0_nCS_SOLE_B") (class "Default")
      (node (ref "R619") (pin "1") (pinfunction "1_1") (pintype "passive"))
    )
    (net (code "195") (name "MCU_SPI0_nCS_SOLE_C") (class "Default")
      (node (ref "R613") (pin "1") (pinfunction "1_1") (pintype "passive"))
    )
    (net (code "196") (name "MCU_SPI0_nCS_SOLE_D") (class "Default")
      (node (ref "R618") (pin "1") (pinfunction "1_1") (pintype "passive"))
    )
    (net (code "197") (name "MCU_SPI0_nCS_SOLE_E") (class "Default")
      (node (ref "R614") (pin "2") (pinfunction "2_2") (pintype "passive"))
    )
    (net (code "198") (name "MCU_SPI1_MISO") (class "Default")
      (node (ref "R103") (pin "2") (pinfunction "2_2") (pintype "passive"))
      (node (ref "R285") (pin "2") (pinfunction "2_2") (pintype "passive"))
    )
    (net (code "199") (name "MCU_SPI1_MOSI") (class "Default")
      (node (ref "R104") (pin "2") (pinfunction "2_2") (pintype "passive"))
    )
    (net (code "200") (name "MCU_SPI1_SCK") (class "Default")
      (node (ref "R102") (pin "2") (pinfunction "2_2") (pintype "passive"))
    )
    (net (code "201") (name "MCU_STATUS_LED_1") (class "Default")
      (node (ref "D36") (pin "2") (pinfunction "A_2") (pintype "passive"))
      (node (ref "R659") (pin "1") (pinfunction "1_1") (pintype "passive"))
      (node (ref "R94") (pin "1") (pinfunction "1_1") (pintype "passive"))
    )
    (net (code "202") (name "MCU_UART0_RX_SOM_TX") (class "Default")
      (node (ref "R24") (pin "2") (pinfunction "2_2") (pintype "passive"))
    )
    (net (code "203") (name "MCU_UART0_TX_SOM_RX") (class "Default")
      (node (ref "R26") (pin "2") (pinfunction "2_2") (pintype "passive"))
    )
    (net (code "204") (name "MCU_USART_RXD2") (class "Default")
      (node (ref "R131") (pin "1") (pinfunction "1_1") (pintype "passive"))
    )
    (net (code "205") (name "MCU_USART_SCK2") (class "Default")
      (node (ref "R39") (pin "1") (pinfunction "1_1") (pintype "passive"))
    )
    (net (code "206") (name "MCU_USART_TXD2") (class "Default")
      (node (ref "R133") (pin "1") (pinfunction "1_1") (pintype "passive"))
    )
    (net (code "207") (name "MCU_WD_DONE") (class "Default")
      (node (ref "R65") (pin "1") (pinfunction "1_1") (pintype "passive"))
    )
    (net (code "208") (name "MCU_WD_WAKE") (class "Default")
      (node (ref "R67") (pin "1") (pinfunction "1_1") (pintype "passive"))
    )
    (net (code "209") (name "MCU_WD_nRESET") (class "Default")
      (node (ref "R303") (pin "2") (pinfunction "2_2") (pintype "passive"))
    )
    (net (code "210") (name "Net-(C15-Pad2)") (class "Default")
      (node (ref "C15") (pin "2") (pinfunction "2_2") (pintype "passive"))
      (node (ref "R303") (pin "1") (pinfunction "1_1") (pintype "passive"))
      (node (ref "R61") (pin "1") (pinfunction "1_1") (pintype "passive"))
      (node (ref "R63") (pin "2") (pinfunction "2_2") (pintype "passive"))
    )
    (net (code "211") (name "Net-(D36-K)") (class "Default")
      (node (ref "D36") (pin "1") (pinfunction "K_1") (pintype "passive"))
      (node (ref "R298") (pin "1") (pinfunction "1_1") (pintype "passive"))
    )
    (net (code "212") (name "Net-(U3-VBG)") (class "Default")
      (node (ref "C18") (pin "2") (pinfunction "2_2") (pintype "passive"))
      (node (ref "R110") (pin "2") (pinfunction "2_2") (pintype "passive"))
      (node (ref "U3") (pin "140") (pinfunction "VBG_140") (pintype "power_in"))
    )
    (net (code "213") (name "PHOTO_ADC_CONV") (class "Default")
      (node (ref "R36") (pin "2") (pinfunction "2_2") (pintype "passive"))
    )
    (net (code "214") (name "PHOTO_ADC_CS") (class "Default")
      (node (ref "R12") (pin "1") (pinfunction "1_1") (pintype "passive"))
    )
    (net (code "215") (name "PHOTO_ADC_EOC") (class "Default")
      (node (ref "R151") (pin "2") (pinfunction "2_2") (pintype "passive"))
    )
    (net (code "217") (name "PHOTO_SPI0_nCS2") (class "Default")
      (node (ref "R31") (pin "1") (pinfunction "1_1") (pintype "passive"))
    )
    (net (code "218") (name "POW_ONOFF_AI") (class "Default")
      (node (ref "R624") (pin "2") (pinfunction "2_2") (pintype "passive"))
    )
    (net (code "219") (name "POW_ONOFF_BUCK_PERI") (class "Default")
      (node (ref "R282") (pin "1") (pinfunction "1_1") (pintype "passive"))
    )
    (net (code "220") (name "POW_ONOFF_HD4") (class "Default")
      (node (ref "R18") (pin "1") (pinfunction "1_1") (pintype "passive"))
    )
    (net (code "221") (name "POW_ONOFF_HEATER") (class "Default")
      (node (ref "R280") (pin "2") (pinfunction "2_2") (pintype "passive"))
    )
    (net (code "222") (name "POW_ONOFF_LP") (class "Default")
      (node (ref "R23") (pin "1") (pinfunction "1_1") (pintype "passive"))
    )
    (net (code "223") (name "POW_ONOFF_SOM") (class "Default")
      (node (ref "R21") (pin "1") (pinfunction "1_1") (pintype "passive"))
    )
    (net (code "224") (name "POW_ONOFF_Solenoid") (class "Default")
      (node (ref "R16") (pin "1") (pinfunction "1_1") (pintype "passive"))
    )
    (net (code "225") (name "POW_ONOFF_TEC") (class "Default")
      (node (ref "R19") (pin "1") (pinfunction "1_1") (pintype "passive"))
    )
    (net (code "226") (name "SENSOR1_EN") (class "Default")
      (node (ref "R76") (pin "2") (pinfunction "2_2") (pintype "passive"))
    )
    (net (code "227") (name "SENSOR2_EN") (class "Default")
      (node (ref "R78") (pin "2") (pinfunction "2_2") (pintype "passive"))
    )
    (net (code "228") (name "SENSOR3_EN") (class "Default")
      (node (ref "R54") (pin "2") (pinfunction "2_2") (pintype "passive"))
    )
    (net (code "229") (name "SENSOR4_EN") (class "Default")
      (node (ref "R56") (pin "2") (pinfunction "2_2") (pintype "passive"))
    )
    (net (code "230") (name "SENSOR5_EN") (class "Default")
      (node (ref "R80") (pin "2") (pinfunction "2_2") (pintype "passive"))
    )
    (net (code "231") (name "SOLENOID_CTR_1") (class "Default")
      (node (ref "R44") (pin "2") (pinfunction "2_2") (pintype "passive"))
    )
    (net (code "232") (name "SOLENOID_CTR_2") (class "Default")
      (node (ref "R46") (pin "2") (pinfunction "2_2") (pintype "passive"))
    )
    (net (code "233") (name "SOLENOID_CTR_3") (class "Default")
      (node (ref "R47") (pin "2") (pinfunction "2_2") (pintype "passive"))
    )
    (net (code "234") (name "SOLENOID_CTR_4") (class "Default")
      (node (ref "R48") (pin "2") (pinfunction "2_2") (pintype "passive"))
    )
    (net (code "235") (name "TEC_SWEN_1") (class "Default")
      (node (ref "R58") (pin "2") (pinfunction "2_2") (pintype "passive"))
    )
    (net (code "236") (name "TEC_SWEN_2") (class "Default")
      (node (ref "R33") (pin "1") (pinfunction "1_1") (pintype "passive"))
    )
    (net (code "237") (name "TEC_SWEN_3") (class "Default")
      (node (ref "R64") (pin "2") (pinfunction "2_2") (pintype "passive"))
    )
    (net (code "238") (name "TEC_SWEN_4") (class "Default")
      (node (ref "R66") (pin "2") (pinfunction "2_2") (pintype "passive"))
    )
    (net (code "239") (name "TEC_nCS_1") (class "Default")
      (node (ref "R95") (pin "2") (pinfunction "2_2") (pintype "passive"))
    )
    (net (code "240") (name "TEC_nCS_2") (class "Default")
      (node (ref "R98") (pin "2") (pinfunction "2_2") (pintype "passive"))
    )
    (net (code "241") (name "TEC_nCS_3") (class "Default")
      (node (ref "R100") (pin "2") (pinfunction "2_2") (pintype "passive"))
    )
    (net (code "242") (name "TEC_nCS_4") (class "Default")
      (node (ref "R29") (pin "1") (pinfunction "1_1") (pintype "passive"))
    )
    (net (code "245") (name "unconnected-(J3-Pad1)") (class "Default")
      (node (ref "J3") (pin "1") (pinfunction "1_1") (pintype "passive"))
    )
    (net (code "246") (name "unconnected-(J3-Pad7)") (class "Default")
      (node (ref "J3") (pin "7") (pinfunction "7_7") (pintype "passive"))
    )
    (net (code "247") (name "unconnected-(U3-PA17-Pad25)") (class "Default")
      (node (ref "U3") (pin "25") (pinfunction "PA17_25") (pintype "bidirectional+no_connect"))
    )
  )
)
